# FPGA.net
KiCad netlist of a schematic drawn in Altium Designer
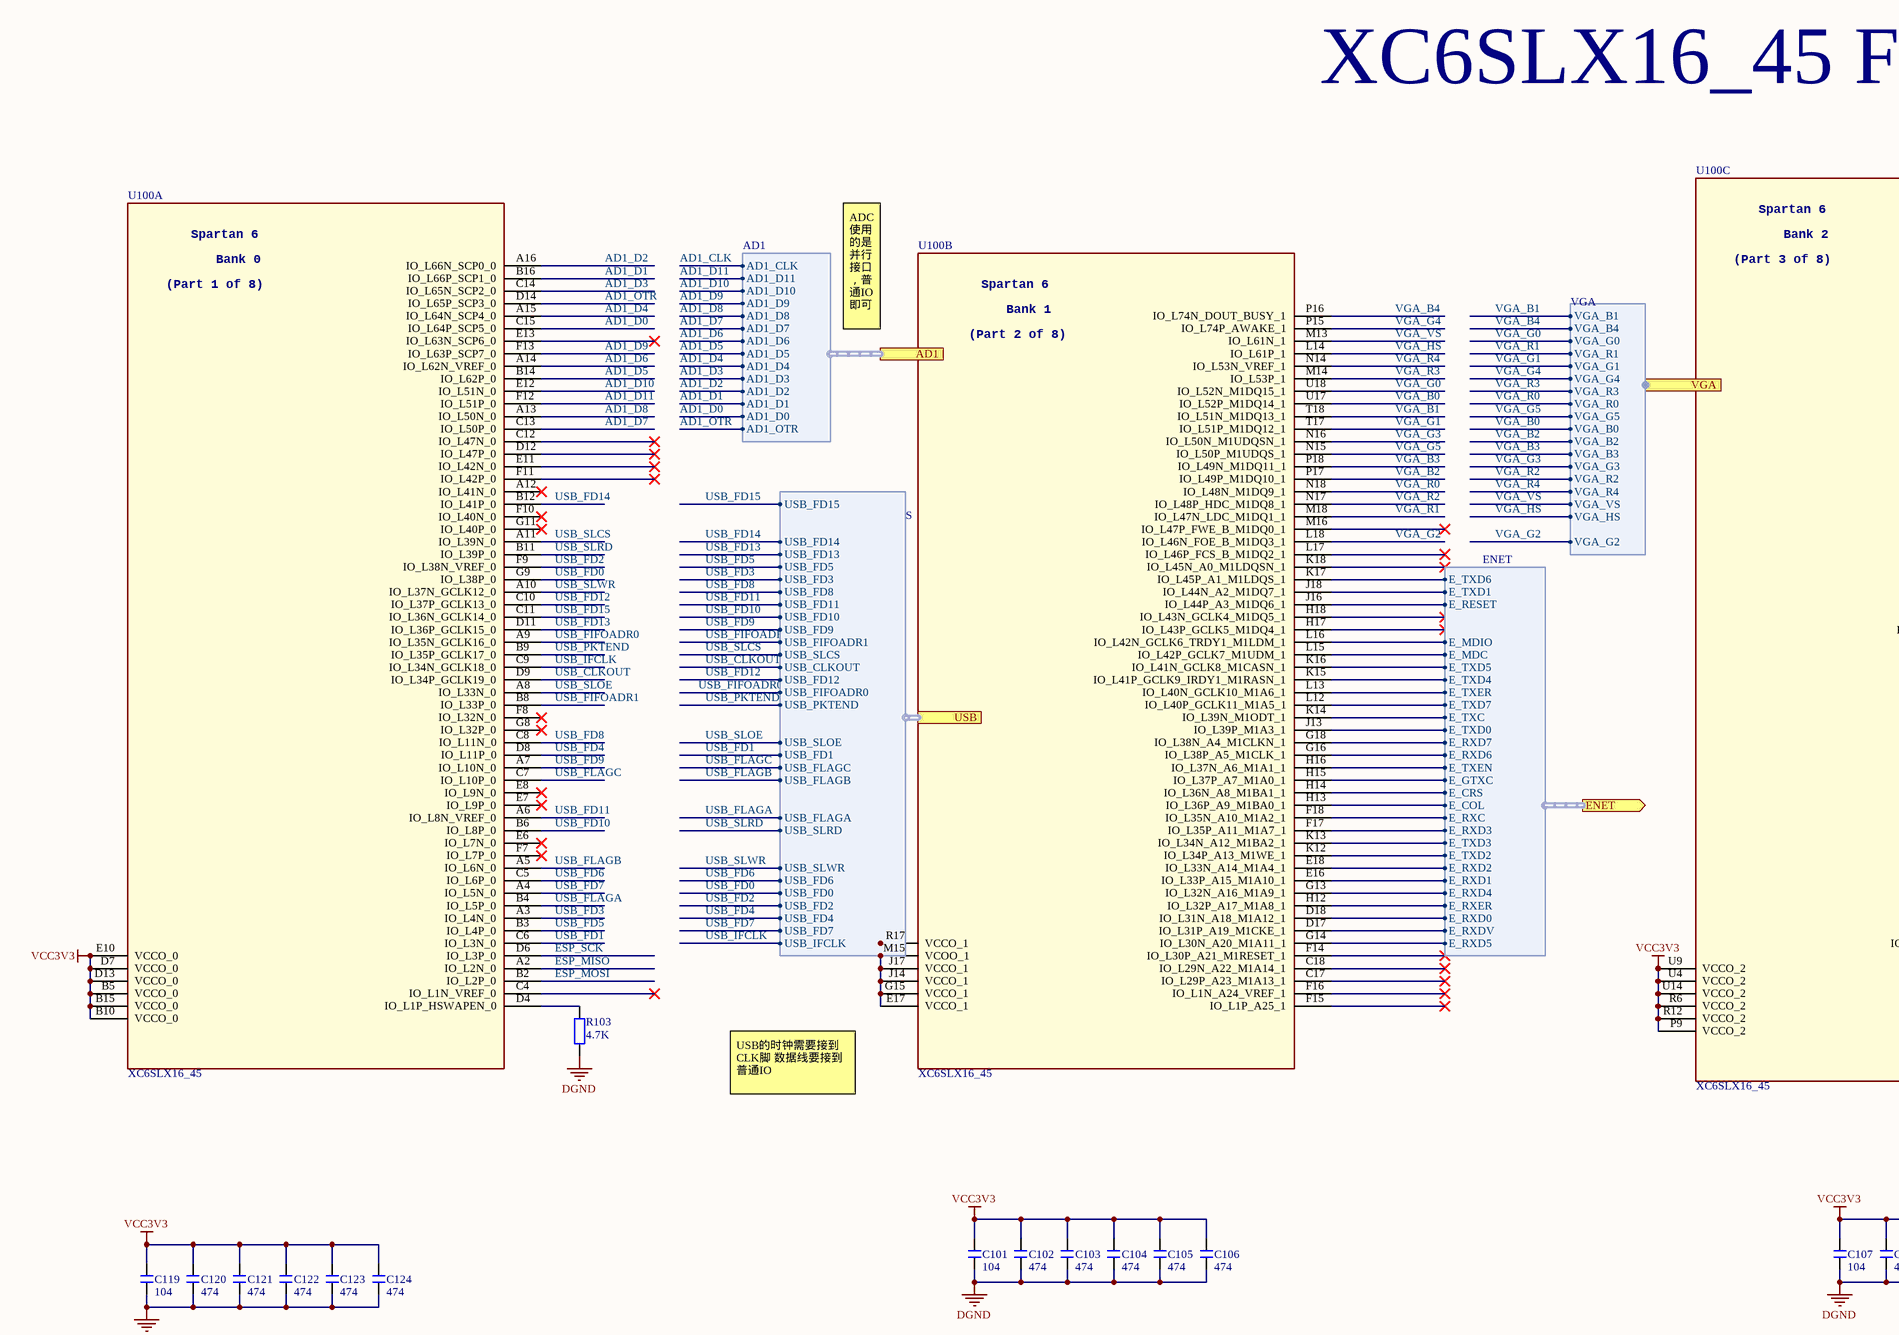
[diagram p0: FPGA.SchDoc, top left]
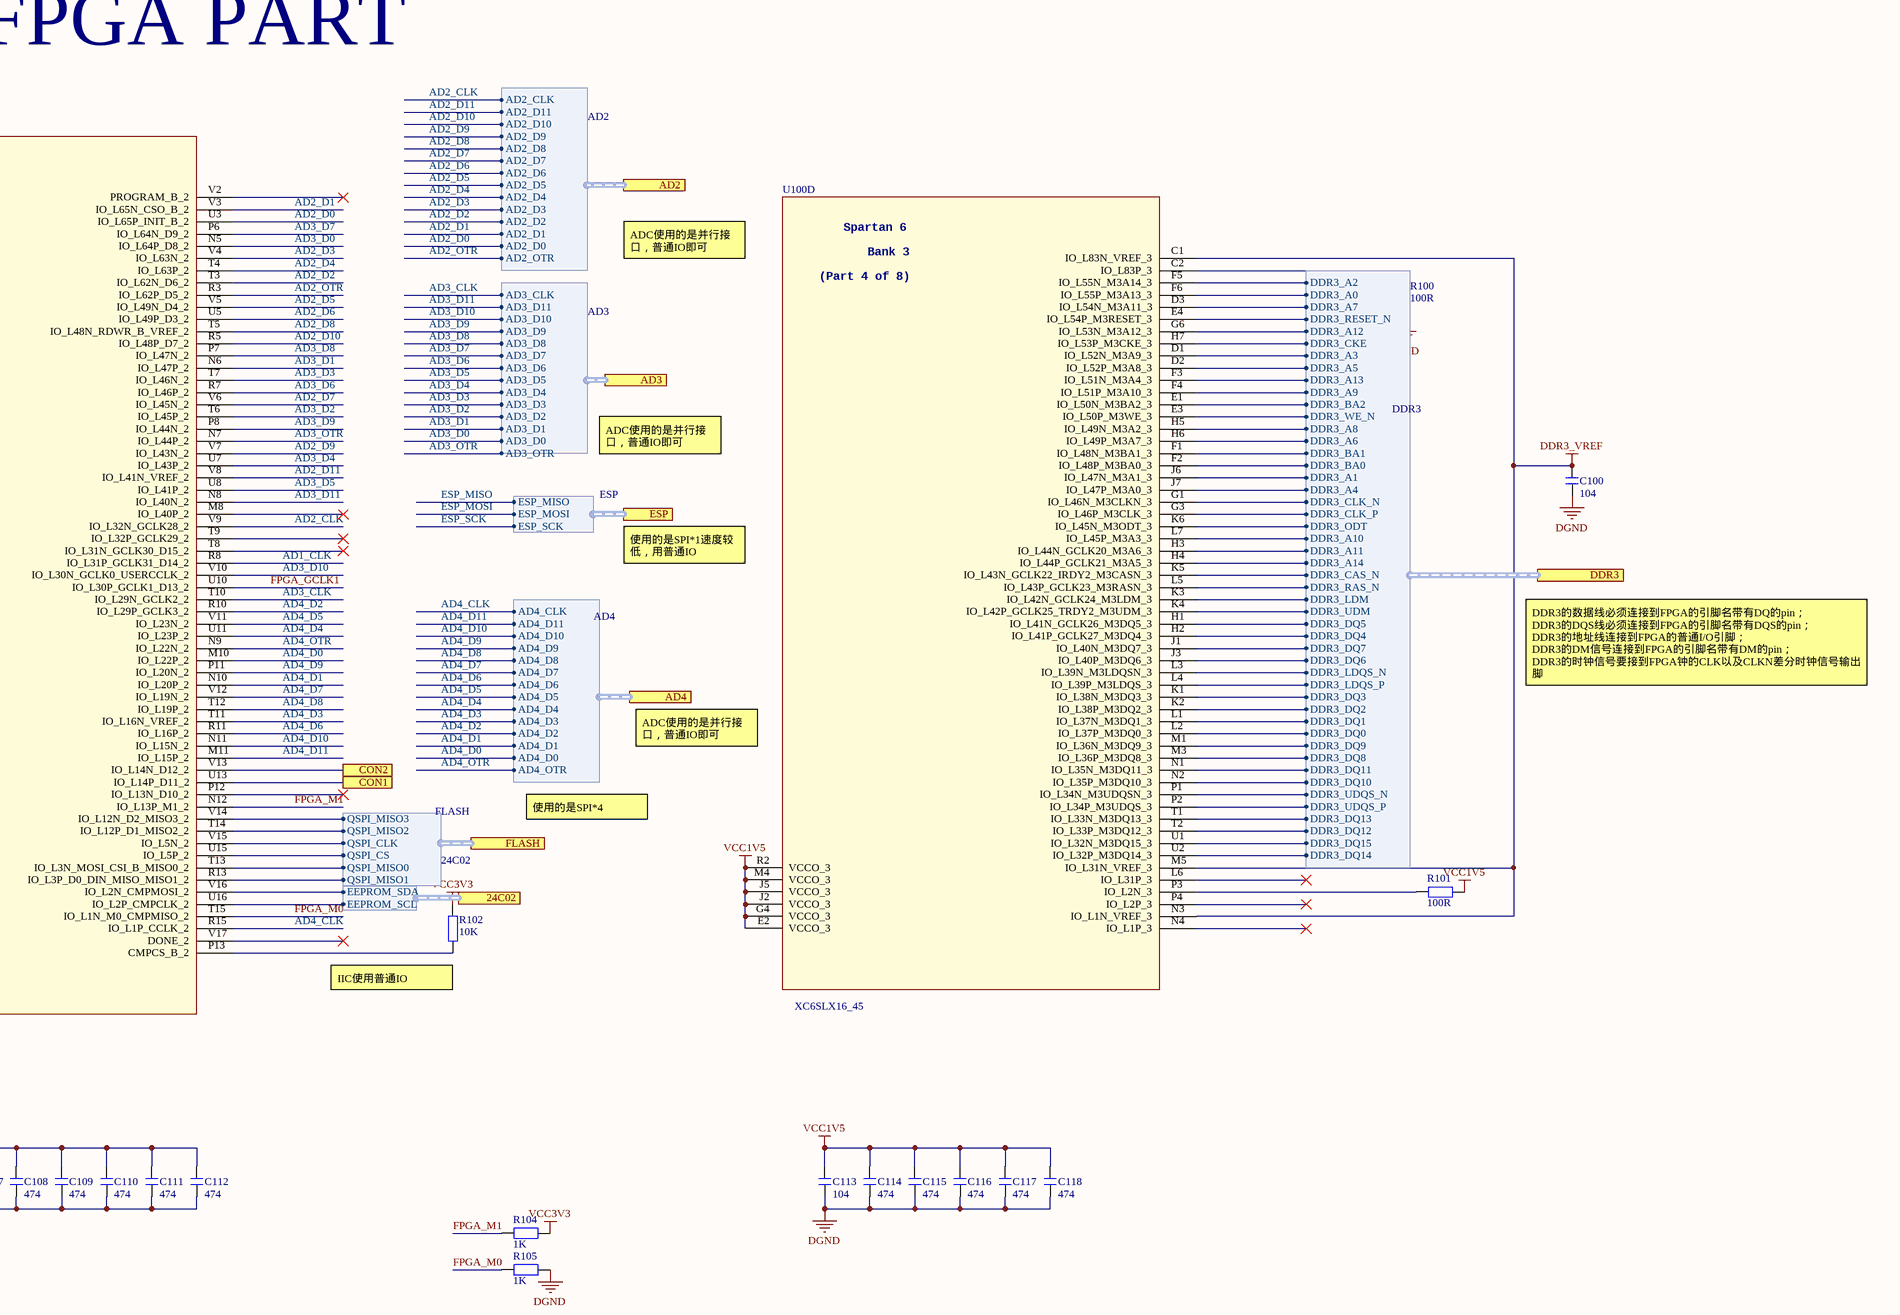
[diagram p1: FPGA.SchDoc, top right]
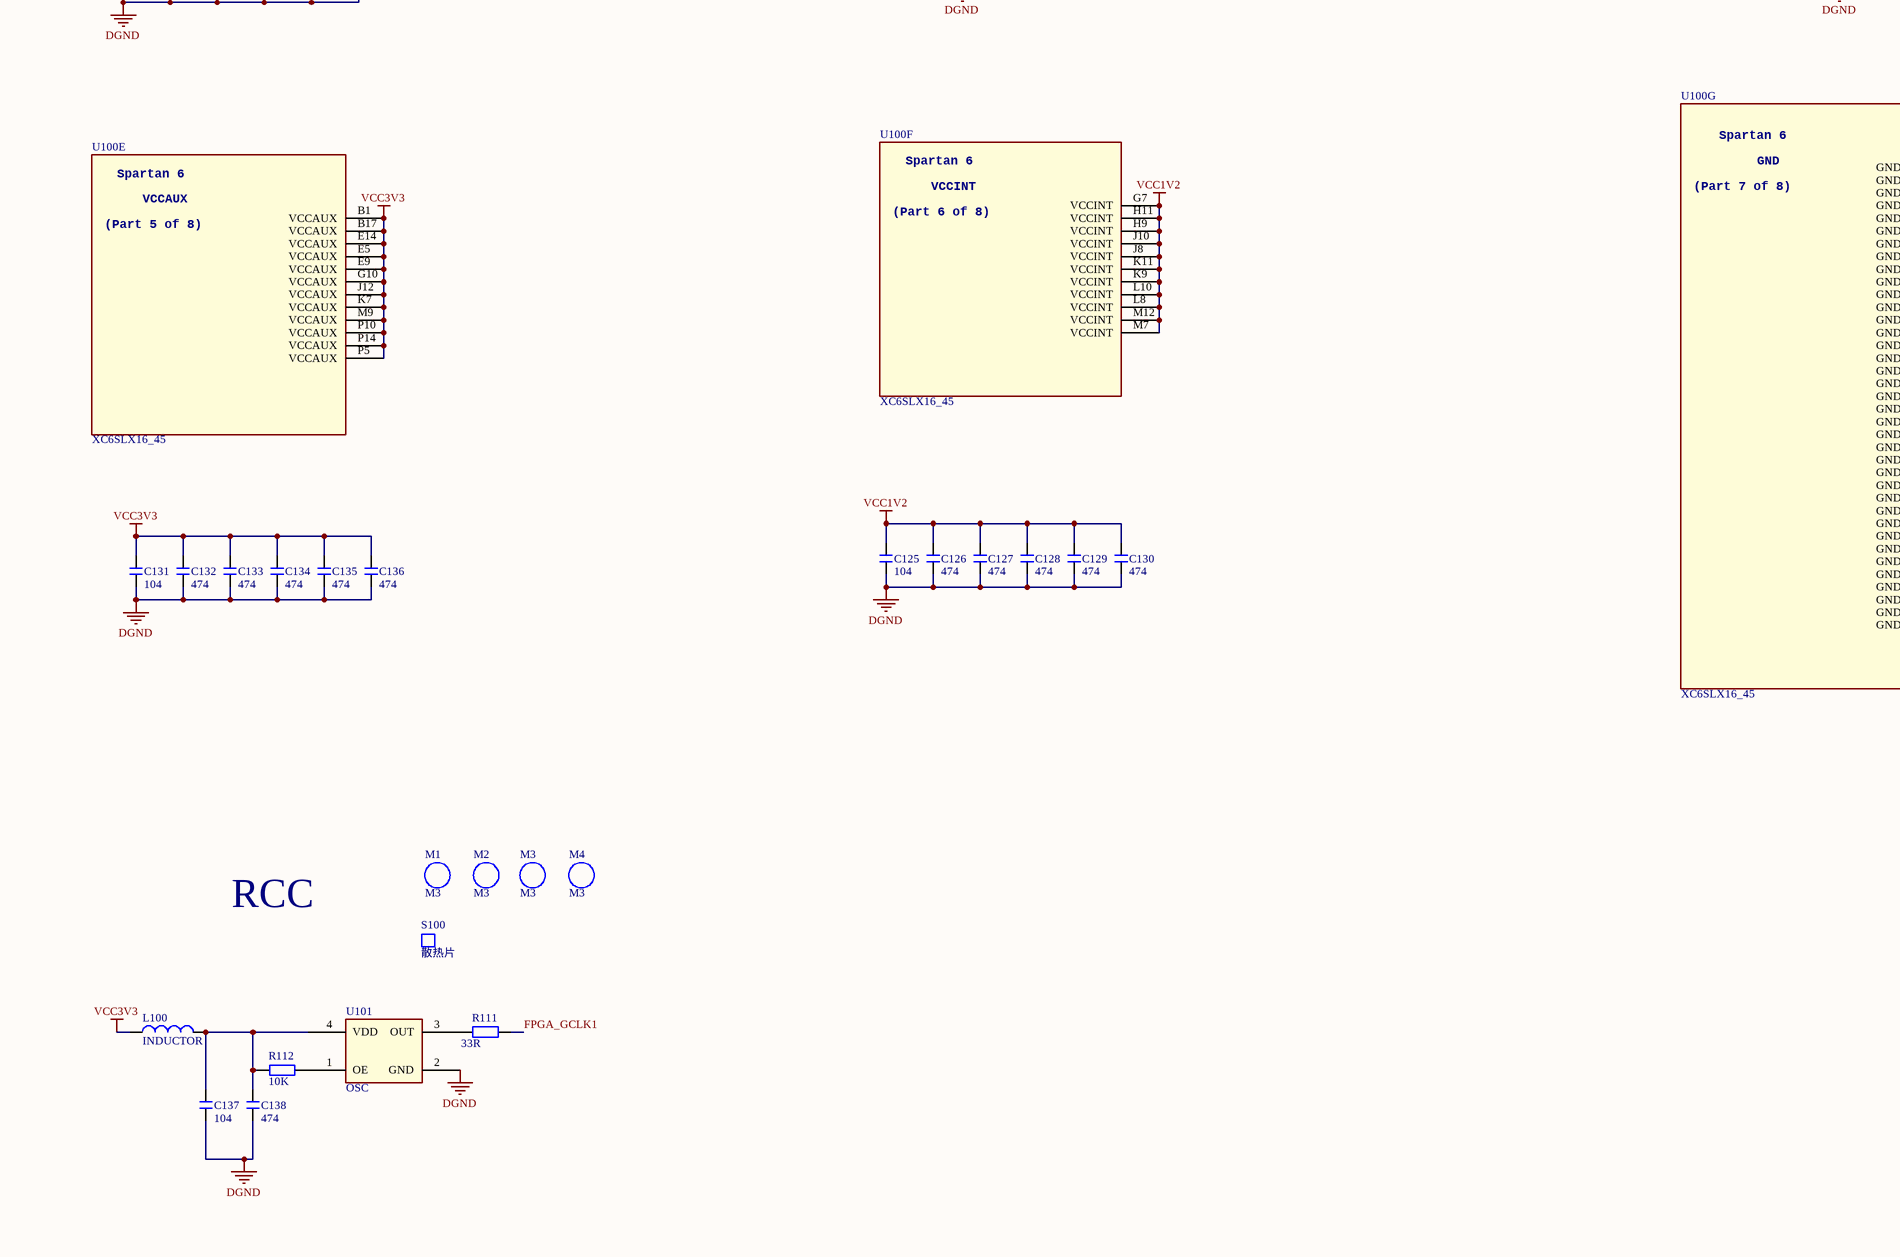
[diagram p2: FPGA.SchDoc, bottom left]
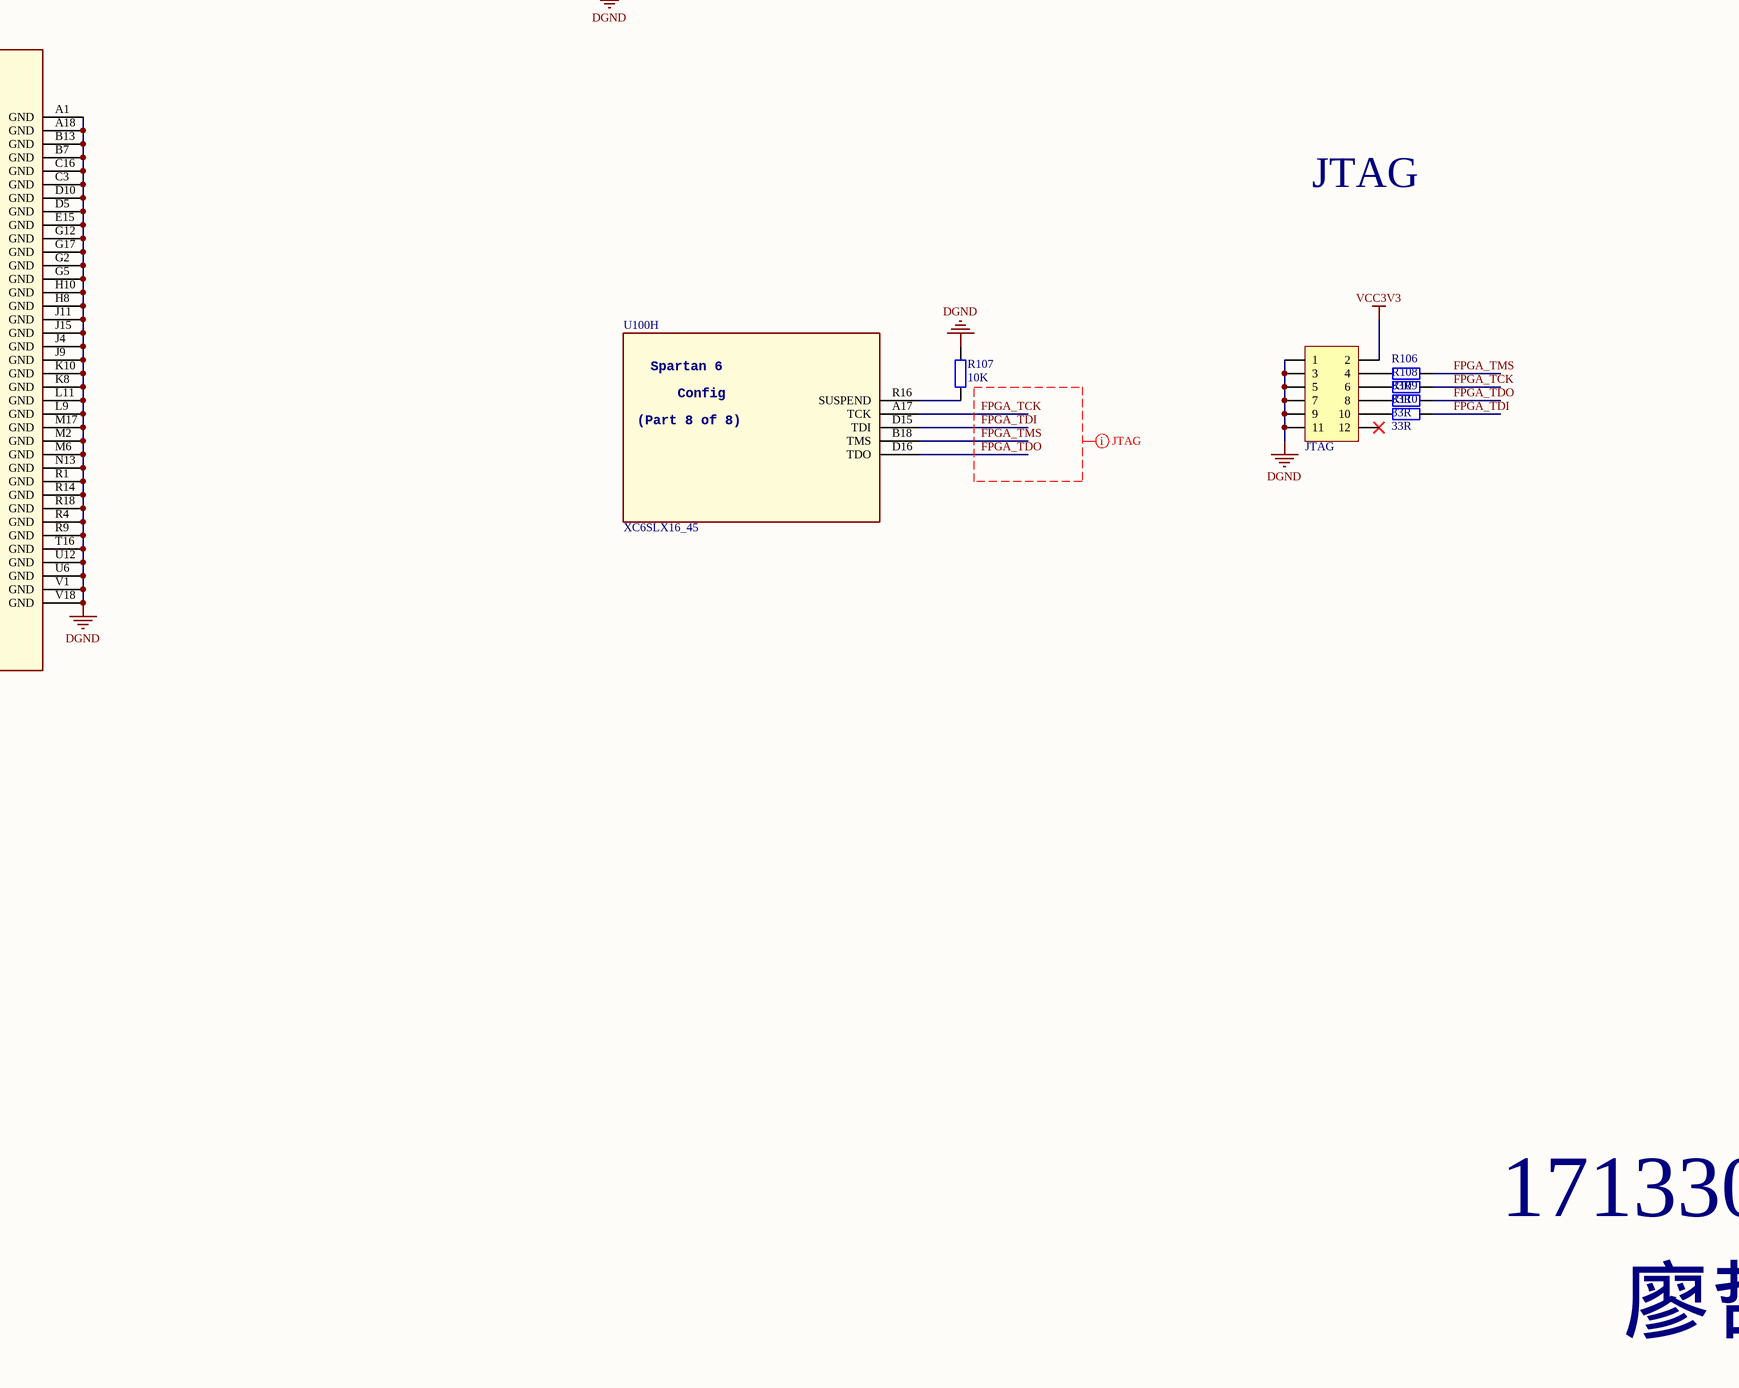
[diagram p3: FPGA.SchDoc, bottom right]

(export (version "E")
  (design (tool "Eeschema 10.0.6"))
  (components
    (comp (ref "C100")
      (value "104")
      (footprint "C 0402_M")
      (description "无极性贴片电容")
      (fields (field (name "版权归属") "源创客"))
      (libsource (lib "3.1   - 电阻-电容-电感") (part "C"))
    )
    (comp (ref "C101")
      (value "104")
      (footprint "C 0402_M")
      (description "无极性贴片电容")
      (fields (field (name "版权归属") "源创客"))
      (libsource (lib "3.1   - 电阻-电容-电感") (part "C"))
    )
    (comp (ref "C102")
      (value "474")
      (footprint "C 0402_M")
      (description "无极性贴片电容")
      (fields (field (name "版权归属") "源创客"))
      (libsource (lib "3.1   - 电阻-电容-电感") (part "C"))
    )
    (comp (ref "C103")
      (value "474")
      (footprint "C 0402_M")
      (description "无极性贴片电容")
      (fields (field (name "版权归属") "源创客"))
      (libsource (lib "3.1   - 电阻-电容-电感") (part "C"))
    )
    (comp (ref "C104")
      (value "474")
      (footprint "C 0402_M")
      (description "无极性贴片电容")
      (fields (field (name "版权归属") "源创客"))
      (libsource (lib "3.1   - 电阻-电容-电感") (part "C"))
    )
    (comp (ref "C105")
      (value "474")
      (footprint "C 0402_M")
      (description "无极性贴片电容")
      (fields (field (name "版权归属") "源创客"))
      (libsource (lib "3.1   - 电阻-电容-电感") (part "C"))
    )
    (comp (ref "C106")
      (value "474")
      (footprint "C 0402_M")
      (description "无极性贴片电容")
      (fields (field (name "版权归属") "源创客"))
      (libsource (lib "3.1   - 电阻-电容-电感") (part "C"))
    )
    (comp (ref "C107")
      (value "104")
      (footprint "C 0402_M")
      (description "无极性贴片电容")
      (fields (field (name "版权归属") "源创客"))
      (libsource (lib "3.1   - 电阻-电容-电感") (part "C"))
    )
    (comp (ref "C108")
      (value "474")
      (footprint "C 0402_M")
      (description "无极性贴片电容")
      (fields (field (name "版权归属") "源创客"))
      (libsource (lib "3.1   - 电阻-电容-电感") (part "C"))
    )
    (comp (ref "C109")
      (value "474")
      (footprint "C 0402_M")
      (description "无极性贴片电容")
      (fields (field (name "版权归属") "源创客"))
      (libsource (lib "3.1   - 电阻-电容-电感") (part "C"))
    )
    (comp (ref "C110")
      (value "474")
      (footprint "C 0402_M")
      (description "无极性贴片电容")
      (fields (field (name "版权归属") "源创客"))
      (libsource (lib "3.1   - 电阻-电容-电感") (part "C"))
    )
    (comp (ref "C111")
      (value "474")
      (footprint "C 0402_M")
      (description "无极性贴片电容")
      (fields (field (name "版权归属") "源创客"))
      (libsource (lib "3.1   - 电阻-电容-电感") (part "C"))
    )
    (comp (ref "C112")
      (value "474")
      (footprint "C 0402_M")
      (description "无极性贴片电容")
      (fields (field (name "版权归属") "源创客"))
      (libsource (lib "3.1   - 电阻-电容-电感") (part "C"))
    )
    (comp (ref "C113")
      (value "104")
      (footprint "C 0402_M")
      (description "无极性贴片电容")
      (fields (field (name "版权归属") "源创客"))
      (libsource (lib "3.1   - 电阻-电容-电感") (part "C"))
    )
    (comp (ref "C114")
      (value "474")
      (footprint "C 0402_M")
      (description "无极性贴片电容")
      (fields (field (name "版权归属") "源创客"))
      (libsource (lib "3.1   - 电阻-电容-电感") (part "C"))
    )
    (comp (ref "C115")
      (value "474")
      (footprint "C 0402_M")
      (description "无极性贴片电容")
      (fields (field (name "版权归属") "源创客"))
      (libsource (lib "3.1   - 电阻-电容-电感") (part "C"))
    )
    (comp (ref "C116")
      (value "474")
      (footprint "C 0402_M")
      (description "无极性贴片电容")
      (fields (field (name "版权归属") "源创客"))
      (libsource (lib "3.1   - 电阻-电容-电感") (part "C"))
    )
    (comp (ref "C117")
      (value "474")
      (footprint "C 0402_M")
      (description "无极性贴片电容")
      (fields (field (name "版权归属") "源创客"))
      (libsource (lib "3.1   - 电阻-电容-电感") (part "C"))
    )
    (comp (ref "C118")
      (value "474")
      (footprint "C 0402_M")
      (description "无极性贴片电容")
      (fields (field (name "版权归属") "源创客"))
      (libsource (lib "3.1   - 电阻-电容-电感") (part "C"))
    )
    (comp (ref "C119")
      (value "104")
      (footprint "C 0402_M")
      (description "无极性贴片电容")
      (fields (field (name "版权归属") "源创客"))
      (libsource (lib "3.1   - 电阻-电容-电感") (part "C"))
    )
    (comp (ref "C120")
      (value "474")
      (footprint "C 0402_M")
      (description "无极性贴片电容")
      (fields (field (name "版权归属") "源创客"))
      (libsource (lib "3.1   - 电阻-电容-电感") (part "C"))
    )
    (comp (ref "C121")
      (value "474")
      (footprint "C 0402_M")
      (description "无极性贴片电容")
      (fields (field (name "版权归属") "源创客"))
      (libsource (lib "3.1   - 电阻-电容-电感") (part "C"))
    )
    (comp (ref "C122")
      (value "474")
      (footprint "C 0402_M")
      (description "无极性贴片电容")
      (fields (field (name "版权归属") "源创客"))
      (libsource (lib "3.1   - 电阻-电容-电感") (part "C"))
    )
    (comp (ref "C123")
      (value "474")
      (footprint "C 0402_M")
      (description "无极性贴片电容")
      (fields (field (name "版权归属") "源创客"))
      (libsource (lib "3.1   - 电阻-电容-电感") (part "C"))
    )
    (comp (ref "C124")
      (value "474")
      (footprint "C 0402_M")
      (description "无极性贴片电容")
      (fields (field (name "版权归属") "源创客"))
      (libsource (lib "3.1   - 电阻-电容-电感") (part "C"))
    )
    (comp (ref "C125")
      (value "104")
      (footprint "C 0402_M")
      (description "无极性贴片电容")
      (fields (field (name "版权归属") "源创客"))
      (libsource (lib "3.1   - 电阻-电容-电感") (part "C"))
    )
    (comp (ref "C126")
      (value "474")
      (footprint "C 0402_M")
      (description "无极性贴片电容")
      (fields (field (name "版权归属") "源创客"))
      (libsource (lib "3.1   - 电阻-电容-电感") (part "C"))
    )
    (comp (ref "C127")
      (value "474")
      (footprint "C 0402_M")
      (description "无极性贴片电容")
      (fields (field (name "版权归属") "源创客"))
      (libsource (lib "3.1   - 电阻-电容-电感") (part "C"))
    )
    (comp (ref "C128")
      (value "474")
      (footprint "C 0402_M")
      (description "无极性贴片电容")
      (fields (field (name "版权归属") "源创客"))
      (libsource (lib "3.1   - 电阻-电容-电感") (part "C"))
    )
    (comp (ref "C129")
      (value "474")
      (footprint "C 0402_M")
      (description "无极性贴片电容")
      (fields (field (name "版权归属") "源创客"))
      (libsource (lib "3.1   - 电阻-电容-电感") (part "C"))
    )
    (comp (ref "C130")
      (value "474")
      (footprint "C 0402_M")
      (description "无极性贴片电容")
      (fields (field (name "版权归属") "源创客"))
      (libsource (lib "3.1   - 电阻-电容-电感") (part "C"))
    )
    (comp (ref "C131")
      (value "104")
      (footprint "C 0402_M")
      (description "无极性贴片电容")
      (fields (field (name "版权归属") "源创客"))
      (libsource (lib "3.1   - 电阻-电容-电感") (part "C"))
    )
    (comp (ref "C132")
      (value "474")
      (footprint "C 0402_M")
      (description "无极性贴片电容")
      (fields (field (name "版权归属") "源创客"))
      (libsource (lib "3.1   - 电阻-电容-电感") (part "C"))
    )
    (comp (ref "C133")
      (value "474")
      (footprint "C 0402_M")
      (description "无极性贴片电容")
      (fields (field (name "版权归属") "源创客"))
      (libsource (lib "3.1   - 电阻-电容-电感") (part "C"))
    )
    (comp (ref "C134")
      (value "474")
      (footprint "C 0402_M")
      (description "无极性贴片电容")
      (fields (field (name "版权归属") "源创客"))
      (libsource (lib "3.1   - 电阻-电容-电感") (part "C"))
    )
    (comp (ref "C135")
      (value "474")
      (footprint "C 0402_M")
      (description "无极性贴片电容")
      (fields (field (name "版权归属") "源创客"))
      (libsource (lib "3.1   - 电阻-电容-电感") (part "C"))
    )
    (comp (ref "C136")
      (value "474")
      (footprint "C 0402_M")
      (description "无极性贴片电容")
      (fields (field (name "版权归属") "源创客"))
      (libsource (lib "3.1   - 电阻-电容-电感") (part "C"))
    )
    (comp (ref "C137")
      (value "104")
      (footprint "C 0402_M")
      (description "无极性贴片电容")
      (fields (field (name "版权归属") "源创客"))
      (libsource (lib "3.1   - 电阻-电容-电感") (part "C"))
    )
    (comp (ref "C138")
      (value "474")
      (footprint "C 0402_M")
      (description "无极性贴片电容")
      (fields (field (name "版权归属") "源创客"))
      (libsource (lib "3.1   - 电阻-电容-电感") (part "C"))
    )
    (comp (ref "JTAG")
      (value "Header 6X2")
      (footprint "IDC2.54-LI-2x6P")
      (description "6*2P接插件")
      (fields (field (name "版权归属") "源创客"))
      (libsource (lib "4.5   - 接插件-脚距2.54") (part "Header  6X2"))
    )
    (comp (ref "L100")
      (value "INDUCTOR")
      (footprint "L 0805")
      (libsource (lib "altium-import") (part "root_1_INDUCTOR_"))
    )
    (comp (ref "M1")
      (value "M3")
      (footprint "M3 140X350")
      (description "铜柱孔")
      (fields (field (name "版权归属") "源创客"))
      (libsource (lib "15.1 - 未分类器件") (part "M3"))
    )
    (comp (ref "M2")
      (value "M3")
      (footprint "M3 140X350")
      (description "铜柱孔")
      (fields (field (name "版权归属") "源创客"))
      (libsource (lib "15.1 - 未分类器件") (part "M3"))
    )
    (comp (ref "M3")
      (value "M3")
      (footprint "M3 140X350")
      (description "铜柱孔")
      (fields (field (name "版权归属") "源创客"))
      (libsource (lib "15.1 - 未分类器件") (part "M3"))
    )
    (comp (ref "M4")
      (value "M3")
      (footprint "M3 140X350")
      (description "铜柱孔")
      (fields (field (name "版权归属") "源创客"))
      (libsource (lib "15.1 - 未分类器件") (part "M3"))
    )
    (comp (ref "R100")
      (value "100R")
      (footprint "R 0402_M")
      (description "贴片电阻")
      (fields (field (name "版权归属") "源创客"))
      (libsource (lib "3.1   - 电阻-电容-电感") (part "R"))
    )
    (comp (ref "R101")
      (value "100R")
      (footprint "R 0402_M")
      (description "贴片电阻")
      (fields (field (name "版权归属") "源创客"))
      (libsource (lib "3.1   - 电阻-电容-电感") (part "R"))
    )
    (comp (ref "R102")
      (value "10K")
      (footprint "R 0402_M")
      (description "贴片电阻")
      (fields (field (name "版权归属") "源创客"))
      (libsource (lib "3.1   - 电阻-电容-电感") (part "R"))
    )
    (comp (ref "R103")
      (value "4.7K")
      (footprint "R 0402_M")
      (description "贴片电阻")
      (fields (field (name "版权归属") "源创客"))
      (libsource (lib "3.1   - 电阻-电容-电感") (part "R"))
    )
    (comp (ref "R104")
      (value "1K")
      (footprint "R 0402_M")
      (description "贴片电阻")
      (fields (field (name "版权归属") "源创客"))
      (libsource (lib "3.1   - 电阻-电容-电感") (part "R"))
    )
    (comp (ref "R105")
      (value "1K")
      (footprint "R 0402_M")
      (description "贴片电阻")
      (fields (field (name "版权归属") "源创客"))
      (libsource (lib "3.1   - 电阻-电容-电感") (part "R"))
    )
    (comp (ref "R106")
      (value "33R")
      (footprint "R 0402_M")
      (description "贴片电阻")
      (fields (field (name "版权归属") "源创客"))
      (libsource (lib "3.1   - 电阻-电容-电感") (part "R"))
    )
    (comp (ref "R107")
      (value "10K")
      (footprint "R 0402_M")
      (description "贴片电阻")
      (fields (field (name "版权归属") "源创客"))
      (libsource (lib "3.1   - 电阻-电容-电感") (part "R"))
    )
    (comp (ref "R108")
      (value "33R")
      (footprint "R 0402_M")
      (description "贴片电阻")
      (fields (field (name "版权归属") "源创客"))
      (libsource (lib "3.1   - 电阻-电容-电感") (part "R"))
    )
    (comp (ref "R109")
      (value "33R")
      (footprint "R 0402_M")
      (description "贴片电阻")
      (fields (field (name "版权归属") "源创客"))
      (libsource (lib "3.1   - 电阻-电容-电感") (part "R"))
    )
    (comp (ref "R110")
      (value "33R")
      (footprint "R 0402_M")
      (description "贴片电阻")
      (fields (field (name "版权归属") "源创客"))
      (libsource (lib "3.1   - 电阻-电容-电感") (part "R"))
    )
    (comp (ref "R111")
      (value "33R")
      (footprint "R 0402_M")
      (description "贴片电阻")
      (fields (field (name "版权归属") "源创客"))
      (libsource (lib "3.1   - 电阻-电容-电感") (part "R"))
    )
    (comp (ref "R112")
      (value "10K")
      (footprint "R 0402_M")
      (description "贴片电阻")
      (fields (field (name "版权归属") "源创客"))
      (libsource (lib "3.1   - 电阻-电容-电感") (part "R"))
    )
    (comp (ref "S100")
      (value "散热片")
      (footprint "SRP10-15-21")
      (fields (field (name "版权归属") "源创客"))
      (libsource (lib "15.1 - 未分类器件") (part "S1"))
    )
    (comp (ref "U100")
      (value "XC6SLX16_45")
      (footprint "BGA324C80P18X18_1500X1500X150")
      (libsource (lib "altium-import") (part "root_0_XC6SLX16_45_"))
    )
    (comp (ref "U101")
      (value "OSC")
      (footprint "OSC 8045-4P")
      (libsource (lib "altium-import") (part "root_0_OSC_"))
    )
  )
  (nets
    (net (code "12") (name "/AD1_CLK") (class "Default")
      (node (ref "U100") (pin "R8") (pinfunction "IO_L31P_GCLK31_D14_2_R8") (pintype "passive"))
    )
    (net (code "13") (name "/AD1_D0") (class "Default")
      (node (ref "U100") (pin "C15") (pinfunction "IO_L64P_SCP5_0_C15") (pintype "passive"))
    )
    (net (code "14") (name "/AD1_D1") (class "Default")
      (node (ref "U100") (pin "B16") (pinfunction "IO_L66P_SCP1_0_B16") (pintype "passive"))
    )
    (net (code "15") (name "/AD1_D2") (class "Default")
      (node (ref "U100") (pin "A16") (pinfunction "IO_L66N_SCP0_0_A16") (pintype "passive"))
    )
    (net (code "16") (name "/AD1_D3") (class "Default")
      (node (ref "U100") (pin "C14") (pinfunction "IO_L65N_SCP2_0_C14") (pintype "passive"))
    )
    (net (code "17") (name "/AD1_D4") (class "Default")
      (node (ref "U100") (pin "A15") (pinfunction "IO_L64N_SCP4_0_A15") (pintype "passive"))
    )
    (net (code "18") (name "/AD1_D5") (class "Default")
      (node (ref "U100") (pin "B14") (pinfunction "IO_L62P_0_B14") (pintype "passive"))
    )
    (net (code "19") (name "/AD1_D6") (class "Default")
      (node (ref "U100") (pin "A14") (pinfunction "IO_L62N_VREF_0_A14") (pintype "passive"))
    )
    (net (code "20") (name "/AD1_D7") (class "Default")
      (node (ref "U100") (pin "C13") (pinfunction "IO_L50P_0_C13") (pintype "passive"))
    )
    (net (code "21") (name "/AD1_D8") (class "Default")
      (node (ref "U100") (pin "A13") (pinfunction "IO_L50N_0_A13") (pintype "passive"))
    )
    (net (code "22") (name "/AD1_D9") (class "Default")
      (node (ref "U100") (pin "F13") (pinfunction "IO_L63P_SCP7_0_F13") (pintype "passive"))
    )
    (net (code "23") (name "/AD1_D10") (class "Default")
      (node (ref "U100") (pin "E12") (pinfunction "IO_L51N_0_E12") (pintype "passive"))
    )
    (net (code "24") (name "/AD1_D11") (class "Default")
      (node (ref "U100") (pin "F12") (pinfunction "IO_L51P_0_F12") (pintype "passive"))
    )
    (net (code "25") (name "/AD1_OTR") (class "Default")
      (node (ref "U100") (pin "D14") (pinfunction "IO_L65P_SCP3_0_D14") (pintype "passive"))
    )
    (net (code "26") (name "/AD2_CLK") (class "Default")
      (node (ref "U100") (pin "V9") (pinfunction "IO_L32N_GCLK28_2_V9") (pintype "passive"))
    )
    (net (code "27") (name "/AD2_D0") (class "Default")
      (node (ref "U100") (pin "U3") (pinfunction "IO_L65P_INIT_B_2_U3") (pintype "passive"))
    )
    (net (code "28") (name "/AD2_D1") (class "Default")
      (node (ref "U100") (pin "V3") (pinfunction "IO_L65N_CSO_B_2_V3") (pintype "passive"))
    )
    (net (code "29") (name "/AD2_D2") (class "Default")
      (node (ref "U100") (pin "T3") (pinfunction "IO_L62N_D6_2_T3") (pintype "passive"))
    )
    (net (code "30") (name "/AD2_D3") (class "Default")
      (node (ref "U100") (pin "V4") (pinfunction "IO_L63N_2_V4") (pintype "passive"))
    )
    (net (code "31") (name "/AD2_D4") (class "Default")
      (node (ref "U100") (pin "T4") (pinfunction "IO_L63P_2_T4") (pintype "passive"))
    )
    (net (code "32") (name "/AD2_D5") (class "Default")
      (node (ref "U100") (pin "V5") (pinfunction "IO_L49N_D4_2_V5") (pintype "passive"))
    )
    (net (code "33") (name "/AD2_D6") (class "Default")
      (node (ref "U100") (pin "U5") (pinfunction "IO_L49P_D3_2_U5") (pintype "passive"))
    )
    (net (code "34") (name "/AD2_D7") (class "Default")
      (node (ref "U100") (pin "V6") (pinfunction "IO_L45N_2_V6") (pintype "passive"))
    )
    (net (code "35") (name "/AD2_D8") (class "Default")
      (node (ref "U100") (pin "T5") (pinfunction "IO_L48N_RDWR_B_VREF_2_T5") (pintype "passive"))
    )
    (net (code "36") (name "/AD2_D9") (class "Default")
      (node (ref "U100") (pin "V7") (pinfunction "IO_L43N_2_V7") (pintype "passive"))
    )
    (net (code "37") (name "/AD2_D10") (class "Default")
      (node (ref "U100") (pin "R5") (pinfunction "IO_L48P_D7_2_R5") (pintype "passive"))
    )
    (net (code "38") (name "/AD2_D11") (class "Default")
      (node (ref "U100") (pin "V8") (pinfunction "IO_L41N_VREF_2_V8") (pintype "passive"))
    )
    (net (code "39") (name "/AD2_OTR") (class "Default")
      (node (ref "U100") (pin "R3") (pinfunction "IO_L62P_D5_2_R3") (pintype "passive"))
    )
    (net (code "40") (name "/AD3_CLK") (class "Default")
      (node (ref "U100") (pin "T10") (pinfunction "IO_L29N_GCLK2_2_T10") (pintype "passive"))
    )
    (net (code "41") (name "/AD3_D0") (class "Default")
      (node (ref "U100") (pin "N5") (pinfunction "IO_L64P_D8_2_N5") (pintype "passive"))
    )
    (net (code "42") (name "/AD3_D1") (class "Default")
      (node (ref "U100") (pin "N6") (pinfunction "IO_L47P_2_N6") (pintype "passive"))
    )
    (net (code "43") (name "/AD3_D2") (class "Default")
      (node (ref "U100") (pin "T6") (pinfunction "IO_L45P_2_T6") (pintype "passive"))
    )
    (net (code "44") (name "/AD3_D3") (class "Default")
      (node (ref "U100") (pin "T7") (pinfunction "IO_L46N_2_T7") (pintype "passive"))
    )
    (net (code "45") (name "/AD3_D4") (class "Default")
      (node (ref "U100") (pin "U7") (pinfunction "IO_L43P_2_U7") (pintype "passive"))
    )
    (net (code "46") (name "/AD3_D5") (class "Default")
      (node (ref "U100") (pin "U8") (pinfunction "IO_L41P_2_U8") (pintype "passive"))
    )
    (net (code "47") (name "/AD3_D6") (class "Default")
      (node (ref "U100") (pin "R7") (pinfunction "IO_L46P_2_R7") (pintype "passive"))
    )
    (net (code "48") (name "/AD3_D7") (class "Default")
      (node (ref "U100") (pin "P6") (pinfunction "IO_L64N_D9_2_P6") (pintype "passive"))
    )
    (net (code "49") (name "/AD3_D8") (class "Default")
      (node (ref "U100") (pin "P7") (pinfunction "IO_L47N_2_P7") (pintype "passive"))
    )
    (net (code "50") (name "/AD3_D9") (class "Default")
      (node (ref "U100") (pin "P8") (pinfunction "IO_L44N_2_P8") (pintype "passive"))
    )
    (net (code "51") (name "/AD3_D10") (class "Default")
      (node (ref "U100") (pin "V10") (pinfunction "IO_L30N_GCLK0_USERCCLK_2_V10") (pintype "passive"))
    )
    (net (code "52") (name "/AD3_D11") (class "Default")
      (node (ref "U100") (pin "N8") (pinfunction "IO_L40N_2_N8") (pintype "passive"))
    )
    (net (code "53") (name "/AD3_OTR") (class "Default")
      (node (ref "U100") (pin "N7") (pinfunction "IO_L44P_2_N7") (pintype "passive"))
    )
    (net (code "54") (name "/AD4_CLK") (class "Default")
      (node (ref "U100") (pin "R15") (pinfunction "IO_L1P_CCLK_2_R15") (pintype "passive"))
    )
    (net (code "55") (name "/AD4_D0") (class "Default")
      (node (ref "U100") (pin "M10") (pinfunction "IO_L22P_2_M10") (pintype "passive"))
    )
    (net (code "56") (name "/AD4_D1") (class "Default")
      (node (ref "U100") (pin "N10") (pinfunction "IO_L20P_2_N10") (pintype "passive"))
    )
    (net (code "57") (name "/AD4_D2") (class "Default")
      (node (ref "U100") (pin "R10") (pinfunction "IO_L29P_GCLK3_2_R10") (pintype "passive"))
    )
    (net (code "58") (name "/AD4_D3") (class "Default")
      (node (ref "U100") (pin "T11") (pinfunction "IO_L16N_VREF_2_T11") (pintype "passive"))
    )
    (net (code "59") (name "/AD4_D4") (class "Default")
      (node (ref "U100") (pin "U11") (pinfunction "IO_L23P_2_U11") (pintype "passive"))
    )
    (net (code "60") (name "/AD4_D5") (class "Default")
      (node (ref "U100") (pin "V11") (pinfunction "IO_L23N_2_V11") (pintype "passive"))
    )
    (net (code "61") (name "/AD4_D6") (class "Default")
      (node (ref "U100") (pin "R11") (pinfunction "IO_L16P_2_R11") (pintype "passive"))
    )
    (net (code "62") (name "/AD4_D7") (class "Default")
      (node (ref "U100") (pin "V12") (pinfunction "IO_L19N_2_V12") (pintype "passive"))
    )
    (net (code "63") (name "/AD4_D8") (class "Default")
      (node (ref "U100") (pin "T12") (pinfunction "IO_L19P_2_T12") (pintype "passive"))
    )
    (net (code "64") (name "/AD4_D9") (class "Default")
      (node (ref "U100") (pin "P11") (pinfunction "IO_L20N_2_P11") (pintype "passive"))
    )
    (net (code "65") (name "/AD4_D10") (class "Default")
      (node (ref "U100") (pin "N11") (pinfunction "IO_L15N_2_N11") (pintype "passive"))
    )
    (net (code "66") (name "/AD4_D11") (class "Default")
      (node (ref "U100") (pin "M11") (pinfunction "IO_L15P_2_M11") (pintype "passive"))
    )
    (net (code "67") (name "/AD4_OTR") (class "Default")
      (node (ref "U100") (pin "N9") (pinfunction "IO_L22N_2_N9") (pintype "passive"))
    )
    (net (code "68") (name "/CON1") (class "Default")
      (node (ref "U100") (pin "U13") (pinfunction "IO_L14P_D11_2_U13") (pintype "passive"))
    )
    (net (code "69") (name "/CON2") (class "Default")
      (node (ref "U100") (pin "V13") (pinfunction "IO_L14N_D12_2_V13") (pintype "passive"))
    )
    (net (code "70") (name "/DDR3_A0") (class "Default")
      (node (ref "U100") (pin "F6") (pinfunction "IO_L55P_M3A13_3_F6") (pintype "passive"))
    )
    (net (code "71") (name "/DDR3_A1") (class "Default")
      (node (ref "U100") (pin "J6") (pinfunction "IO_L47N_M3A1_3_J6") (pintype "passive"))
    )
    (net (code "72") (name "/DDR3_A2") (class "Default")
      (node (ref "U100") (pin "F5") (pinfunction "IO_L55N_M3A14_3_F5") (pintype "passive"))
    )
    (net (code "73") (name "/DDR3_A3") (class "Default")
      (node (ref "U100") (pin "D1") (pinfunction "IO_L52N_M3A9_3_D1") (pintype "passive"))
    )
    (net (code "74") (name "/DDR3_A4") (class "Default")
      (node (ref "U100") (pin "J7") (pinfunction "IO_L47P_M3A0_3_J7") (pintype "passive"))
    )
    (net (code "75") (name "/DDR3_A5") (class "Default")
      (node (ref "U100") (pin "D2") (pinfunction "IO_L52P_M3A8_3_D2") (pintype "passive"))
    )
    (net (code "76") (name "/DDR3_A6") (class "Default")
      (node (ref "U100") (pin "H6") (pinfunction "IO_L49P_M3A7_3_H6") (pintype "passive"))
    )
    (net (code "77") (name "/DDR3_A7") (class "Default")
      (node (ref "U100") (pin "D3") (pinfunction "IO_L54N_M3A11_3_D3") (pintype "passive"))
    )
    (net (code "78") (name "/DDR3_A8") (class "Default")
      (node (ref "U100") (pin "H5") (pinfunction "IO_L49N_M3A2_3_H5") (pintype "passive"))
    )
    (net (code "79") (name "/DDR3_A9") (class "Default")
      (node (ref "U100") (pin "F4") (pinfunction "IO_L51P_M3A10_3_F4") (pintype "passive"))
    )
    (net (code "80") (name "/DDR3_A10") (class "Default")
      (node (ref "U100") (pin "L7") (pinfunction "IO_L45P_M3A3_3_L7") (pintype "passive"))
    )
    (net (code "81") (name "/DDR3_A11") (class "Default")
      (node (ref "U100") (pin "H3") (pinfunction "IO_L44N_GCLK20_M3A6_3_H3") (pintype "passive"))
    )
    (net (code "82") (name "/DDR3_A12") (class "Default")
      (node (ref "U100") (pin "G6") (pinfunction "IO_L53N_M3A12_3_G6") (pintype "passive"))
    )
    (net (code "83") (name "/DDR3_A13") (class "Default")
      (node (ref "U100") (pin "F3") (pinfunction "IO_L51N_M3A4_3_F3") (pintype "passive"))
    )
    (net (code "84") (name "/DDR3_A14") (class "Default")
      (node (ref "U100") (pin "H4") (pinfunction "IO_L44P_GCLK21_M3A5_3_H4") (pintype "passive"))
    )
    (net (code "85") (name "/DDR3_BA0") (class "Default")
      (node (ref "U100") (pin "F2") (pinfunction "IO_L48P_M3BA0_3_F2") (pintype "passive"))
    )
    (net (code "86") (name "/DDR3_BA1") (class "Default")
      (node (ref "U100") (pin "F1") (pinfunction "IO_L48N_M3BA1_3_F1") (pintype "passive"))
    )
    (net (code "87") (name "/DDR3_BA2") (class "Default")
      (node (ref "U100") (pin "E1") (pinfunction "IO_L50N_M3BA2_3_E1") (pintype "passive"))
    )
    (net (code "88") (name "/DDR3_CAS_N") (class "Default")
      (node (ref "U100") (pin "K5") (pinfunction "IO_L43N_GCLK22_IRDY2_M3CASN_3_K5") (pintype "passive"))
    )
    (net (code "89") (name "/DDR3_CKE") (class "Default")
      (node (ref "U100") (pin "H7") (pinfunction "IO_L53P_M3CKE_3_H7") (pintype "passive"))
    )
    (net (code "90") (name "/DDR3_CLK_N") (class "Default")
      (node (ref "U100") (pin "G1") (pinfunction "IO_L46N_M3CLKN_3_G1") (pintype "passive"))
    )
    (net (code "91") (name "/DDR3_CLK_P") (class "Default")
      (node (ref "U100") (pin "G3") (pinfunction "IO_L46P_M3CLK_3_G3") (pintype "passive"))
    )
    (net (code "92") (name "/DDR3_DQ0") (class "Default")
      (node (ref "U100") (pin "L2") (pinfunction "IO_L37P_M3DQ0_3_L2") (pintype "passive"))
    )
    (net (code "93") (name "/DDR3_DQ1") (class "Default")
      (node (ref "U100") (pin "L1") (pinfunction "IO_L37N_M3DQ1_3_L1") (pintype "passive"))
    )
    (net (code "94") (name "/DDR3_DQ2") (class "Default")
      (node (ref "U100") (pin "K2") (pinfunction "IO_L38P_M3DQ2_3_K2") (pintype "passive"))
    )
    (net (code "95") (name "/DDR3_DQ3") (class "Default")
      (node (ref "U100") (pin "K1") (pinfunction "IO_L38N_M3DQ3_3_K1") (pintype "passive"))
    )
    (net (code "96") (name "/DDR3_DQ4") (class "Default")
      (node (ref "U100") (pin "H2") (pinfunction "IO_L41P_GCLK27_M3DQ4_3_H2") (pintype "passive"))
    )
    (net (code "97") (name "/DDR3_DQ5") (class "Default")
      (node (ref "U100") (pin "H1") (pinfunction "IO_L41N_GCLK26_M3DQ5_3_H1") (pintype "passive"))
    )
    (net (code "98") (name "/DDR3_DQ6") (class "Default")
      (node (ref "U100") (pin "J3") (pinfunction "IO_L40P_M3DQ6_3_J3") (pintype "passive"))
    )
    (net (code "99") (name "/DDR3_DQ7") (class "Default")
      (node (ref "U100") (pin "J1") (pinfunction "IO_L40N_M3DQ7_3_J1") (pintype "passive"))
    )
    (net (code "100") (name "/DDR3_DQ8") (class "Default")
      (node (ref "U100") (pin "M3") (pinfunction "IO_L36P_M3DQ8_3_M3") (pintype "passive"))
    )
    (net (code "101") (name "/DDR3_DQ9") (class "Default")
      (node (ref "U100") (pin "M1") (pinfunction "IO_L36N_M3DQ9_3_M1") (pintype "passive"))
    )
    (net (code "102") (name "/DDR3_DQ10") (class "Default")
      (node (ref "U100") (pin "N2") (pinfunction "IO_L35P_M3DQ10_3_N2") (pintype "passive"))
    )
    (net (code "103") (name "/DDR3_DQ11") (class "Default")
      (node (ref "U100") (pin "N1") (pinfunction "IO_L35N_M3DQ11_3_N1") (pintype "passive"))
    )
    (net (code "104") (name "/DDR3_DQ12") (class "Default")
      (node (ref "U100") (pin "T2") (pinfunction "IO_L33P_M3DQ12_3_T2") (pintype "passive"))
    )
    (net (code "105") (name "/DDR3_DQ13") (class "Default")
      (node (ref "U100") (pin "T1") (pinfunction "IO_L33N_M3DQ13_3_T1") (pintype "passive"))
    )
    (net (code "106") (name "/DDR3_DQ14") (class "Default")
      (node (ref "U100") (pin "U2") (pinfunction "IO_L32P_M3DQ14_3_U2") (pintype "passive"))
    )
    (net (code "107") (name "/DDR3_DQ15") (class "Default")
      (node (ref "U100") (pin "U1") (pinfunction "IO_L32N_M3DQ15_3_U1") (pintype "passive"))
    )
    (net (code "108") (name "/DDR3_LDM") (class "Default")
      (node (ref "U100") (pin "K3") (pinfunction "IO_L42N_GCLK24_M3LDM_3_K3") (pintype "passive"))
    )
    (net (code "109") (name "/DDR3_LDQS_N") (class "Default")
      (node (ref "U100") (pin "L3") (pinfunction "IO_L39N_M3LDQSN_3_L3") (pintype "passive"))
    )
    (net (code "110") (name "/DDR3_LDQS_P") (class "Default")
      (node (ref "U100") (pin "L4") (pinfunction "IO_L39P_M3LDQS_3_L4") (pintype "passive"))
    )
    (net (code "111") (name "/DDR3_ODT") (class "Default")
      (node (ref "U100") (pin "K6") (pinfunction "IO_L45N_M3ODT_3_K6") (pintype "passive"))
    )
    (net (code "112") (name "/DDR3_RAS_N") (class "Default")
      (node (ref "U100") (pin "L5") (pinfunction "IO_L43P_GCLK23_M3RASN_3_L5") (pintype "passive"))
    )
    (net (code "113") (name "/DDR3_RESET_N") (class "Default")
      (node (ref "U100") (pin "E4") (pinfunction "IO_L54P_M3RESET_3_E4") (pintype "passive"))
    )
    (net (code "114") (name "/DDR3_UDM") (class "Default")
      (node (ref "U100") (pin "K4") (pinfunction "IO_L42P_GCLK25_TRDY2_M3UDM_3_K4") (pintype "passive"))
    )
    (net (code "115") (name "/DDR3_UDQS_N") (class "Default")
      (node (ref "U100") (pin "P1") (pinfunction "IO_L34N_M3UDQSN_3_P1") (pintype "passive"))
    )
    (net (code "116") (name "/DDR3_UDQS_P") (class "Default")
      (node (ref "U100") (pin "P2") (pinfunction "IO_L34P_M3UDQS_3_P2") (pintype "passive"))
    )
    (net (code "117") (name "/DDR3_WE_N") (class "Default")
      (node (ref "U100") (pin "E3") (pinfunction "IO_L50P_M3WE_3_E3") (pintype "passive"))
    )
    (net (code "118") (name "/EEPROM_SCL") (class "Default")
      (node (ref "U100") (pin "U16") (pinfunction "IO_L2P_CMPCLK_2_U16") (pintype "passive"))
    )
    (net (code "119") (name "/EEPROM_SDA") (class "Default")
      (node (ref "U100") (pin "V16") (pinfunction "IO_L2N_CMPMOSI_2_V16") (pintype "passive"))
    )
    (net (code "120") (name "/ESP_MISO") (class "Default")
      (node (ref "U100") (pin "A2") (pinfunction "IO_L2N_0_A2") (pintype "passive"))
    )
    (net (code "121") (name "/ESP_MOSI") (class "Default")
      (node (ref "U100") (pin "B2") (pinfunction "IO_L2P_0_B2") (pintype "passive"))
    )
    (net (code "122") (name "/ESP_SCK") (class "Default")
      (node (ref "U100") (pin "D6") (pinfunction "IO_L3P_0_D6") (pintype "passive"))
    )
    (net (code "123") (name "/E_COL") (class "Default")
      (node (ref "U100") (pin "H13") (pinfunction "IO_L36P_A9_M1BA0_1_H13") (pintype "passive"))
    )
    (net (code "124") (name "/E_CRS") (class "Default")
      (node (ref "U100") (pin "H14") (pinfunction "IO_L36N_A8_M1BA1_1_H14") (pintype "passive"))
    )
    (net (code "125") (name "/E_GTXC") (class "Default")
      (node (ref "U100") (pin "H15") (pinfunction "IO_L37P_A7_M1A0_1_H15") (pintype "passive"))
    )
    (net (code "126") (name "/E_MDC") (class "Default")
      (node (ref "U100") (pin "L15") (pinfunction "IO_L42P_GCLK7_M1UDM_1_L15") (pintype "passive"))
    )
    (net (code "127") (name "/E_MDIO") (class "Default")
      (node (ref "U100") (pin "L16") (pinfunction "IO_L42N_GCLK6_TRDY1_M1LDM_1_L16") (pintype "passive"))
    )
    (net (code "128") (name "/E_RESET") (class "Default")
      (node (ref "U100") (pin "J16") (pinfunction "IO_L44P_A3_M1DQ6_1_J16") (pintype "passive"))
    )
    (net (code "129") (name "/E_RXC") (class "Default")
      (node (ref "U100") (pin "F18") (pinfunction "IO_L35N_A10_M1A2_1_F18") (pintype "passive"))
    )
    (net (code "130") (name "/E_RXD0") (class "Default")
      (node (ref "U100") (pin "D18") (pinfunction "IO_L31N_A18_M1A12_1_D18") (pintype "passive"))
    )
    (net (code "131") (name "/E_RXD1") (class "Default")
      (node (ref "U100") (pin "E16") (pinfunction "IO_L33P_A15_M1A10_1_E16") (pintype "passive"))
    )
    (net (code "132") (name "/E_RXD2") (class "Default")
      (node (ref "U100") (pin "E18") (pinfunction "IO_L33N_A14_M1A4_1_E18") (pintype "passive"))
    )
    (net (code "133") (name "/E_RXD3") (class "Default")
      (node (ref "U100") (pin "F17") (pinfunction "IO_L35P_A11_M1A7_1_F17") (pintype "passive"))
    )
    (net (code "134") (name "/E_RXD4") (class "Default")
      (node (ref "U100") (pin "G13") (pinfunction "IO_L32N_A16_M1A9_1_G13") (pintype "passive"))
    )
    (net (code "135") (name "/E_RXD5") (class "Default")
      (node (ref "U100") (pin "G14") (pinfunction "IO_L30N_A20_M1A11_1_G14") (pintype "passive"))
    )
    (net (code "136") (name "/E_RXD6") (class "Default")
      (node (ref "U100") (pin "G16") (pinfunction "IO_L38P_A5_M1CLK_1_G16") (pintype "passive"))
    )
    (net (code "137") (name "/E_RXD7") (class "Default")
      (node (ref "U100") (pin "G18") (pinfunction "IO_L38N_A4_M1CLKN_1_G18") (pintype "passive"))
    )
    (net (code "138") (name "/E_RXDV") (class "Default")
      (node (ref "U100") (pin "D17") (pinfunction "IO_L31P_A19_M1CKE_1_D17") (pintype "passive"))
    )
    (net (code "139") (name "/E_RXER") (class "Default")
      (node (ref "U100") (pin "H12") (pinfunction "IO_L32P_A17_M1A8_1_H12") (pintype "passive"))
    )
    (net (code "140") (name "/E_TXC") (class "Default")
      (node (ref "U100") (pin "K14") (pinfunction "IO_L39N_M1ODT_1_K14") (pintype "passive"))
    )
    (net (code "141") (name "/E_TXD0") (class "Default")
      (node (ref "U100") (pin "J13") (pinfunction "IO_L39P_M1A3_1_J13") (pintype "passive"))
    )
    (net (code "142") (name "/E_TXD1") (class "Default")
      (node (ref "U100") (pin "J18") (pinfunction "IO_L44N_A2_M1DQ7_1_J18") (pintype "passive"))
    )
    (net (code "143") (name "/E_TXD2") (class "Default")
      (node (ref "U100") (pin "K12") (pinfunction "IO_L34P_A13_M1WE_1_K12") (pintype "passive"))
    )
    (net (code "144") (name "/E_TXD3") (class "Default")
      (node (ref "U100") (pin "K13") (pinfunction "IO_L34N_A12_M1BA2_1_K13") (pintype "passive"))
    )
    (net (code "145") (name "/E_TXD4") (class "Default")
      (node (ref "U100") (pin "K15") (pinfunction "IO_L41P_GCLK9_IRDY1_M1RASN_1_K15") (pintype "passive"))
    )
    (net (code "146") (name "/E_TXD5") (class "Default")
      (node (ref "U100") (pin "K16") (pinfunction "IO_L41N_GCLK8_M1CASN_1_K16") (pintype "passive"))
    )
    (net (code "147") (name "/E_TXD6") (class "Default")
      (node (ref "U100") (pin "K17") (pinfunction "IO_L45P_A1_M1LDQS_1_K17") (pintype "passive"))
    )
    (net (code "148") (name "/E_TXD7") (class "Default")
      (node (ref "U100") (pin "L12") (pinfunction "IO_L40P_GCLK11_M1A5_1_L12") (pintype "passive"))
    )
    (net (code "149") (name "/E_TXEN") (class "Default")
      (node (ref "U100") (pin "H16") (pinfunction "IO_L37N_A6_M1A1_1_H16") (pintype "passive"))
    )
    (net (code "150") (name "/E_TXER") (class "Default")
      (node (ref "U100") (pin "L13") (pinfunction "IO_L40N_GCLK10_M1A6_1_L13") (pintype "passive"))
    )
    (net (code "151") (name "/FPGA_GCLK1") (class "Default")
      (node (ref "R111") (pin "2") (pinfunction "2_2") (pintype "passive"))
      (node (ref "U100") (pin "U10") (pinfunction "IO_L30P_GCLK1_D13_2_U10") (pintype "passive"))
    )
    (net (code "152") (name "/FPGA_M0") (class "Default")
      (node (ref "R105") (pin "1") (pinfunction "1_1") (pintype "passive"))
      (node (ref "U100") (pin "T15") (pinfunction "IO_L1N_M0_CMPMISO_2_T15") (pintype "passive"))
    )
    (net (code "153") (name "/FPGA_M1") (class "Default")
      (node (ref "R104") (pin "1") (pinfunction "1_1") (pintype "passive"))
      (node (ref "U100") (pin "N12") (pinfunction "IO_L13P_M1_2_N12") (pintype "passive"))
    )
    (net (code "154") (name "/FPGA_TCK") (class "Default")
      (node (ref "R108") (pin "2") (pinfunction "2_2") (pintype "passive"))
      (node (ref "U100") (pin "A17") (pinfunction "TCK_A17") (pintype "passive"))
    )
    (net (code "155") (name "/FPGA_TDI") (class "Default")
      (node (ref "R110") (pin "2") (pinfunction "2_2") (pintype "passive"))
      (node (ref "U100") (pin "D15") (pinfunction "TDI_D15") (pintype "passive"))
    )
    (net (code "156") (name "/FPGA_TDO") (class "Default")
      (node (ref "R109") (pin "2") (pinfunction "2_2") (pintype "passive"))
      (node (ref "U100") (pin "D16") (pinfunction "TDO_D16") (pintype "passive"))
    )
    (net (code "157") (name "/FPGA_TMS") (class "Default")
      (node (ref "R106") (pin "2") (pinfunction "2_2") (pintype "passive"))
      (node (ref "U100") (pin "B18") (pinfunction "TMS_B18") (pintype "passive"))
    )
    (net (code "158") (name "/QSPI_CLK") (class "Default")
      (node (ref "U100") (pin "V15") (pinfunction "IO_L5N_2_V15") (pintype "passive"))
    )
    (net (code "159") (name "/QSPI_CS") (class "Default")
      (node (ref "U100") (pin "U15") (pinfunction "IO_L5P_2_U15") (pintype "passive"))
    )
    (net (code "160") (name "/QSPI_MISO0") (class "Default")
      (node (ref "U100") (pin "T13") (pinfunction "IO_L3N_MOSI_CSI_B_MISO0_2_T13") (pintype "passive"))
    )
    (net (code "161") (name "/QSPI_MISO1") (class "Default")
      (node (ref "U100") (pin "R13") (pinfunction "IO_L3P_D0_DIN_MISO_MISO1_2_R13") (pintype "passive"))
    )
    (net (code "162") (name "/QSPI_MISO2") (class "Default")
      (node (ref "U100") (pin "T14") (pinfunction "IO_L12P_D1_MISO2_2_T14") (pintype "passive"))
    )
    (net (code "163") (name "/QSPI_MISO3") (class "Default")
      (node (ref "U100") (pin "V14") (pinfunction "IO_L12N_D2_MISO3_2_V14") (pintype "passive"))
    )
    (net (code "164") (name "/USB_CLKOUT") (class "Default")
      (node (ref "U100") (pin "D9") (pinfunction "IO_L34P_GCLK19_0_D9") (pintype "passive"))
    )
    (net (code "165") (name "/USB_FD0") (class "Default")
      (node (ref "U100") (pin "G9") (pinfunction "IO_L38P_0_G9") (pintype "passive"))
    )
    (net (code "166") (name "/USB_FD1") (class "Default")
      (node (ref "U100") (pin "C6") (pinfunction "IO_L3N_0_C6") (pintype "passive"))
    )
    (net (code "167") (name "/USB_FD2") (class "Default")
      (node (ref "U100") (pin "F9") (pinfunction "IO_L38N_VREF_0_F9") (pintype "passive"))
    )
    (net (code "168") (name "/USB_FD3") (class "Default")
      (node (ref "U100") (pin "A3") (pinfunction "IO_L4N_0_A3") (pintype "passive"))
    )
    (net (code "169") (name "/USB_FD4") (class "Default")
      (node (ref "U100") (pin "D8") (pinfunction "IO_L11P_0_D8") (pintype "passive"))
    )
    (net (code "170") (name "/USB_FD5") (class "Default")
      (node (ref "U100") (pin "B3") (pinfunction "IO_L4P_0_B3") (pintype "passive"))
    )
    (net (code "171") (name "/USB_FD6") (class "Default")
      (node (ref "U100") (pin "C5") (pinfunction "IO_L6P_0_C5") (pintype "passive"))
    )
    (net (code "172") (name "/USB_FD7") (class "Default")
      (node (ref "U100") (pin "A4") (pinfunction "IO_L5N_0_A4") (pintype "passive"))
    )
    (net (code "173") (name "/USB_FD8") (class "Default")
      (node (ref "U100") (pin "C8") (pinfunction "IO_L11N_0_C8") (pintype "passive"))
    )
    (net (code "174") (name "/USB_FD9") (class "Default")
      (node (ref "U100") (pin "A7") (pinfunction "IO_L10N_0_A7") (pintype "passive"))
    )
    (net (code "175") (name "/USB_FD10") (class "Default")
      (node (ref "U100") (pin "B6") (pinfunction "IO_L8P_0_B6") (pintype "passive"))
    )
    (net (code "176") (name "/USB_FD11") (class "Default")
      (node (ref "U100") (pin "A6") (pinfunction "IO_L8N_VREF_0_A6") (pintype "passive"))
    )
    (net (code "177") (name "/USB_FD12") (class "Default")
      (node (ref "U100") (pin "C10") (pinfunction "IO_L37P_GCLK13_0_C10") (pintype "passive"))
    )
    (net (code "178") (name "/USB_FD13") (class "Default")
      (node (ref "U100") (pin "D11") (pinfunction "IO_L36P_GCLK15_0_D11") (pintype "passive"))
    )
    (net (code "179") (name "/USB_FD14") (class "Default")
      (node (ref "U100") (pin "B12") (pinfunction "IO_L41P_0_B12") (pintype "passive"))
    )
    (net (code "180") (name "/USB_FD15") (class "Default")
      (node (ref "U100") (pin "C11") (pinfunction "IO_L36N_GCLK14_0_C11") (pintype "passive"))
    )
    (net (code "181") (name "/USB_FIFOADR0") (class "Default")
      (node (ref "U100") (pin "A9") (pinfunction "IO_L35N_GCLK16_0_A9") (pintype "passive"))
    )
    (net (code "182") (name "/USB_FIFOADR1") (class "Default")
      (node (ref "U100") (pin "B8") (pinfunction "IO_L33P_0_B8") (pintype "passive"))
    )
    (net (code "183") (name "/USB_FLAGA") (class "Default")
      (node (ref "U100") (pin "B4") (pinfunction "IO_L5P_0_B4") (pintype "passive"))
    )
    (net (code "184") (name "/USB_FLAGB") (class "Default")
      (node (ref "U100") (pin "A5") (pinfunction "IO_L6N_0_A5") (pintype "passive"))
    )
    (net (code "185") (name "/USB_FLAGC") (class "Default")
      (node (ref "U100") (pin "C7") (pinfunction "IO_L10P_0_C7") (pintype "passive"))
    )
    (net (code "186") (name "/USB_IFCLK") (class "Default")
      (node (ref "U100") (pin "C9") (pinfunction "IO_L34N_GCLK18_0_C9") (pintype "passive"))
    )
    (net (code "187") (name "/USB_PKTEND") (class "Default")
      (node (ref "U100") (pin "B9") (pinfunction "IO_L35P_GCLK17_0_B9") (pintype "passive"))
    )
    (net (code "188") (name "/USB_SLCS") (class "Default")
      (node (ref "U100") (pin "A11") (pinfunction "IO_L39N_0_A11") (pintype "passive"))
    )
    (net (code "189") (name "/USB_SLOE") (class "Default")
      (node (ref "U100") (pin "A8") (pinfunction "IO_L33N_0_A8") (pintype "passive"))
    )
    (net (code "190") (name "/USB_SLRD") (class "Default")
      (node (ref "U100") (pin "B11") (pinfunction "IO_L39P_0_B11") (pintype "passive"))
    )
    (net (code "191") (name "/USB_SLWR") (class "Default")
      (node (ref "U100") (pin "A10") (pinfunction "IO_L37N_GCLK12_0_A10") (pintype "passive"))
    )
    (net (code "192") (name "/VGA_B0") (class "Default")
      (node (ref "U100") (pin "U17") (pinfunction "IO_L52P_M1DQ14_1_U17") (pintype "passive"))
    )
    (net (code "193") (name "/VGA_B1") (class "Default")
      (node (ref "U100") (pin "T18") (pinfunction "IO_L51N_M1DQ13_1_T18") (pintype "passive"))
    )
    (net (code "194") (name "/VGA_B2") (class "Default")
      (node (ref "U100") (pin "P17") (pinfunction "IO_L49P_M1DQ10_1_P17") (pintype "passive"))
    )
    (net (code "195") (name "/VGA_B3") (class "Default")
      (node (ref "U100") (pin "P18") (pinfunction "IO_L49N_M1DQ11_1_P18") (pintype "passive"))
    )
    (net (code "196") (name "/VGA_B4") (class "Default")
      (node (ref "U100") (pin "P16") (pinfunction "IO_L74N_DOUT_BUSY_1_P16") (pintype "passive"))
    )
    (net (code "197") (name "/VGA_G0") (class "Default")
      (node (ref "U100") (pin "U18") (pinfunction "IO_L52N_M1DQ15_1_U18") (pintype "passive"))
    )
    (net (code "198") (name "/VGA_G1") (class "Default")
      (node (ref "U100") (pin "T17") (pinfunction "IO_L51P_M1DQ12_1_T17") (pintype "passive"))
    )
    (net (code "199") (name "/VGA_G2") (class "Default")
      (node (ref "U100") (pin "L18") (pinfunction "IO_L46N_FOE_B_M1DQ3_1_L18") (pintype "passive"))
    )
    (net (code "200") (name "/VGA_G3") (class "Default")
      (node (ref "U100") (pin "N16") (pinfunction "IO_L50N_M1UDQSN_1_N16") (pintype "passive"))
    )
    (net (code "201") (name "/VGA_G4") (class "Default")
      (node (ref "U100") (pin "P15") (pinfunction "IO_L74P_AWAKE_1_P15") (pintype "passive"))
    )
    (net (code "202") (name "/VGA_G5") (class "Default")
      (node (ref "U100") (pin "N15") (pinfunction "IO_L50P_M1UDQS_1_N15") (pintype "passive"))
    )
    (net (code "203") (name "/VGA_HS") (class "Default")
      (node (ref "U100") (pin "L14") (pinfunction "IO_L61P_1_L14") (pintype "passive"))
    )
    (net (code "204") (name "/VGA_R0") (class "Default")
      (node (ref "U100") (pin "N18") (pinfunction "IO_L48N_M1DQ9_1_N18") (pintype "passive"))
    )
    (net (code "205") (name "/VGA_R1") (class "Default")
      (node (ref "U100") (pin "M18") (pinfunction "IO_L47N_LDC_M1DQ1_1_M18") (pintype "passive"))
    )
    (net (code "206") (name "/VGA_R2") (class "Default")
      (node (ref "U100") (pin "N17") (pinfunction "IO_L48P_HDC_M1DQ8_1_N17") (pintype "passive"))
    )
    (net (code "207") (name "/VGA_R3") (class "Default")
      (node (ref "U100") (pin "M14") (pinfunction "IO_L53P_1_M14") (pintype "passive"))
    )
    (net (code "208") (name "/VGA_R4") (class "Default")
      (node (ref "U100") (pin "N14") (pinfunction "IO_L53N_VREF_1_N14") (pintype "passive"))
    )
    (net (code "209") (name "/VGA_VS") (class "Default")
      (node (ref "U100") (pin "M13") (pinfunction "IO_L61N_1_M13") (pintype "passive"))
    )
    (net (code "221") (name "DDR3_VREF") (class "Default")
      (node (ref "C100") (pin "2") (pinfunction "2_2") (pintype "passive"))
      (node (ref "U100") (pin "C1") (pinfunction "IO_L83N_VREF_3_C1") (pintype "passive"))
      (node (ref "U100") (pin "M5") (pinfunction "IO_L31N_VREF_3_M5") (pintype "passive"))
      (node (ref "U100") (pin "N3") (pinfunction "IO_L1N_VREF_3_N3") (pintype "passive"))
    )
    (net (code "222") (name "DGND") (class "Default")
      (node (ref "C100") (pin "1") (pinfunction "1_1") (pintype "passive"))
      (node (ref "C101") (pin "1") (pinfunction "1_1") (pintype "passive"))
      (node (ref "C102") (pin "1") (pinfunction "1_1") (pintype "passive"))
      (node (ref "C103") (pin "1") (pinfunction "1_1") (pintype "passive"))
      (node (ref "C104") (pin "1") (pinfunction "1_1") (pintype "passive"))
      (node (ref "C105") (pin "1") (pinfunction "1_1") (pintype "passive"))
      (node (ref "C106") (pin "1") (pinfunction "1_1") (pintype "passive"))
      (node (ref "C107") (pin "1") (pinfunction "1_1") (pintype "passive"))
      (node (ref "C108") (pin "1") (pinfunction "1_1") (pintype "passive"))
      (node (ref "C109") (pin "1") (pinfunction "1_1") (pintype "passive"))
      (node (ref "C110") (pin "1") (pinfunction "1_1") (pintype "passive"))
      (node (ref "C111") (pin "1") (pinfunction "1_1") (pintype "passive"))
      (node (ref "C112") (pin "1") (pinfunction "1_1") (pintype "passive"))
      (node (ref "C113") (pin "1") (pinfunction "1_1") (pintype "passive"))
      (node (ref "C114") (pin "1") (pinfunction "1_1") (pintype "passive"))
      (node (ref "C115") (pin "1") (pinfunction "1_1") (pintype "passive"))
      (node (ref "C116") (pin "1") (pinfunction "1_1") (pintype "passive"))
      (node (ref "C117") (pin "1") (pinfunction "1_1") (pintype "passive"))
      (node (ref "C118") (pin "1") (pinfunction "1_1") (pintype "passive"))
      (node (ref "C119") (pin "1") (pinfunction "1_1") (pintype "passive"))
      (node (ref "C120") (pin "1") (pinfunction "1_1") (pintype "passive"))
      (node (ref "C121") (pin "1") (pinfunction "1_1") (pintype "passive"))
      (node (ref "C122") (pin "1") (pinfunction "1_1") (pintype "passive"))
      (node (ref "C123") (pin "1") (pinfunction "1_1") (pintype "passive"))
      (node (ref "C124") (pin "1") (pinfunction "1_1") (pintype "passive"))
      (node (ref "C125") (pin "1") (pinfunction "1_1") (pintype "passive"))
      (node (ref "C126") (pin "1") (pinfunction "1_1") (pintype "passive"))
      (node (ref "C127") (pin "1") (pinfunction "1_1") (pintype "passive"))
      (node (ref "C128") (pin "1") (pinfunction "1_1") (pintype "passive"))
      (node (ref "C129") (pin "1") (pinfunction "1_1") (pintype "passive"))
      (node (ref "C130") (pin "1") (pinfunction "1_1") (pintype "passive"))
      (node (ref "C131") (pin "1") (pinfunction "1_1") (pintype "passive"))
      (node (ref "C132") (pin "1") (pinfunction "1_1") (pintype "passive"))
      (node (ref "C133") (pin "1") (pinfunction "1_1") (pintype "passive"))
      (node (ref "C134") (pin "1") (pinfunction "1_1") (pintype "passive"))
      (node (ref "C135") (pin "1") (pinfunction "1_1") (pintype "passive"))
      (node (ref "C136") (pin "1") (pinfunction "1_1") (pintype "passive"))
      (node (ref "C137") (pin "1") (pinfunction "1_1") (pintype "passive"))
      (node (ref "C138") (pin "1") (pinfunction "1_1") (pintype "passive"))
      (node (ref "JTAG") (pin "1") (pinfunction "1_1") (pintype "passive"))
      (node (ref "JTAG") (pin "11") (pinfunction "11_11") (pintype "passive"))
      (node (ref "JTAG") (pin "3") (pinfunction "3_3") (pintype "passive"))
      (node (ref "JTAG") (pin "5") (pinfunction "5_5") (pintype "passive"))
      (node (ref "JTAG") (pin "7") (pinfunction "7_7") (pintype "passive"))
      (node (ref "JTAG") (pin "9") (pinfunction "9_9") (pintype "passive"))
      (node (ref "R100") (pin "1") (pinfunction "1_1") (pintype "passive"))
      (node (ref "R103") (pin "1") (pinfunction "1_1") (pintype "passive"))
      (node (ref "R105") (pin "2") (pinfunction "2_2") (pintype "passive"))
      (node (ref "R107") (pin "1") (pinfunction "1_1") (pintype "passive"))
      (node (ref "U100") (pin "A1") (pinfunction "GND_A1") (pintype "power_in"))
      (node (ref "U100") (pin "A18") (pinfunction "GND_A18") (pintype "power_in"))
      (node (ref "U100") (pin "B13") (pinfunction "GND_B13") (pintype "power_in"))
      (node (ref "U100") (pin "B7") (pinfunction "GND_B7") (pintype "power_in"))
      (node (ref "U100") (pin "C16") (pinfunction "GND_C16") (pintype "power_in"))
      (node (ref "U100") (pin "C3") (pinfunction "GND_C3") (pintype "power_in"))
      (node (ref "U100") (pin "D10") (pinfunction "GND_D10") (pintype "power_in"))
      (node (ref "U100") (pin "D5") (pinfunction "GND_D5") (pintype "power_in"))
      (node (ref "U100") (pin "E15") (pinfunction "GND_E15") (pintype "power_in"))
      (node (ref "U100") (pin "G12") (pinfunction "GND_G12") (pintype "power_in"))
      (node (ref "U100") (pin "G17") (pinfunction "GND_G17") (pintype "power_in"))
      (node (ref "U100") (pin "G2") (pinfunction "GND_G2") (pintype "power_in"))
      (node (ref "U100") (pin "G5") (pinfunction "GND_G5") (pintype "power_in"))
      (node (ref "U100") (pin "H10") (pinfunction "GND_H10") (pintype "power_in"))
      (node (ref "U100") (pin "H8") (pinfunction "GND_H8") (pintype "power_in"))
      (node (ref "U100") (pin "J11") (pinfunction "GND_J11") (pintype "power_in"))
      (node (ref "U100") (pin "J15") (pinfunction "GND_J15") (pintype "power_in"))
      (node (ref "U100") (pin "J4") (pinfunction "GND_J4") (pintype "power_in"))
      (node (ref "U100") (pin "J9") (pinfunction "GND_J9") (pintype "power_in"))
      (node (ref "U100") (pin "K10") (pinfunction "GND_K10") (pintype "power_in"))
      (node (ref "U100") (pin "K8") (pinfunction "GND_K8") (pintype "power_in"))
      (node (ref "U100") (pin "L11") (pinfunction "GND_L11") (pintype "power_in"))
      (node (ref "U100") (pin "L9") (pinfunction "GND_L9") (pintype "power_in"))
      (node (ref "U100") (pin "M17") (pinfunction "GND_M17") (pintype "power_in"))
      (node (ref "U100") (pin "M2") (pinfunction "GND_M2") (pintype "power_in"))
      (node (ref "U100") (pin "M6") (pinfunction "GND_M6") (pintype "power_in"))
      (node (ref "U100") (pin "N13") (pinfunction "GND_N13") (pintype "power_in"))
      (node (ref "U100") (pin "R1") (pinfunction "GND_R1") (pintype "power_in"))
      (node (ref "U100") (pin "R14") (pinfunction "GND_R14") (pintype "power_in"))
      (node (ref "U100") (pin "R18") (pinfunction "GND_R18") (pintype "power_in"))
      (node (ref "U100") (pin "R4") (pinfunction "GND_R4") (pintype "power_in"))
      (node (ref "U100") (pin "R9") (pinfunction "GND_R9") (pintype "power_in"))
      (node (ref "U100") (pin "T16") (pinfunction "GND_T16") (pintype "power_in"))
      (node (ref "U100") (pin "U12") (pinfunction "GND_U12") (pintype "power_in"))
      (node (ref "U100") (pin "U6") (pinfunction "GND_U6") (pintype "power_in"))
      (node (ref "U100") (pin "V1") (pinfunction "GND_V1") (pintype "power_in"))
      (node (ref "U100") (pin "V18") (pinfunction "GND_V18") (pintype "power_in"))
      (node (ref "U101") (pin "2") (pinfunction "GND_2") (pintype "passive"))
    )
    (net (code "223") (name "Net-(JTAG-Pad4)") (class "Default")
      (node (ref "JTAG") (pin "4") (pinfunction "4_4") (pintype "passive"))
      (node (ref "R106") (pin "1") (pinfunction "1_1") (pintype "passive"))
    )
    (net (code "224") (name "Net-(JTAG-Pad6)") (class "Default")
      (node (ref "JTAG") (pin "6") (pinfunction "6_6") (pintype "passive"))
      (node (ref "R108") (pin "1") (pinfunction "1_1") (pintype "passive"))
    )
    (net (code "225") (name "Net-(JTAG-Pad8)") (class "Default")
      (node (ref "JTAG") (pin "8") (pinfunction "8_8") (pintype "passive"))
      (node (ref "R109") (pin "1") (pinfunction "1_1") (pintype "passive"))
    )
    (net (code "226") (name "Net-(JTAG-Pad10)") (class "Default")
      (node (ref "JTAG") (pin "10") (pinfunction "10_10") (pintype "passive"))
      (node (ref "R110") (pin "1") (pinfunction "1_1") (pintype "passive"))
    )
    (net (code "227") (name "Net-(U100A-IO_L1P_HSWAPEN_0)") (class "Default")
      (node (ref "R103") (pin "2") (pinfunction "2_2") (pintype "passive"))
      (node (ref "U100") (pin "D4") (pinfunction "IO_L1P_HSWAPEN_0_D4") (pintype "passive"))
    )
    (net (code "228") (name "Net-(U100C-CMPCS_B_2)") (class "Default")
      (node (ref "R102") (pin "2") (pinfunction "2_2") (pintype "passive"))
      (node (ref "U100") (pin "P13") (pinfunction "CMPCS_B_2_P13") (pintype "passive"))
    )
    (net (code "229") (name "Net-(U100D-IO_L2N_3)") (class "Default")
      (node (ref "R101") (pin "2") (pinfunction "2_2") (pintype "passive"))
      (node (ref "U100") (pin "P3") (pinfunction "IO_L2N_3_P3") (pintype "passive"))
    )
    (net (code "230") (name "Net-(U100D-IO_L83P_3)") (class "Default")
      (node (ref "R100") (pin "2") (pinfunction "2_2") (pintype "passive"))
      (node (ref "U100") (pin "C2") (pinfunction "IO_L83P_3_C2") (pintype "passive"))
    )
    (net (code "231") (name "Net-(U100H-SUSPEND)") (class "Default")
      (node (ref "R107") (pin "2") (pinfunction "2_2") (pintype "passive"))
      (node (ref "U100") (pin "R16") (pinfunction "SUSPEND_R16") (pintype "passive"))
    )
    (net (code "232") (name "Net-(U101-OE)") (class "Default")
      (node (ref "R112") (pin "2") (pinfunction "2_2") (pintype "passive"))
      (node (ref "U101") (pin "1") (pinfunction "OE_1") (pintype "passive"))
    )
    (net (code "233") (name "Net-(U101-OUT)") (class "Default")
      (node (ref "R111") (pin "1") (pinfunction "1_1") (pintype "passive"))
      (node (ref "U101") (pin "3") (pinfunction "OUT_3") (pintype "passive"))
    )
    (net (code "234") (name "Net-(U101-VDD)") (class "Default")
      (node (ref "C137") (pin "2") (pinfunction "2_2") (pintype "passive"))
      (node (ref "C138") (pin "2") (pinfunction "2_2") (pintype "passive"))
      (node (ref "L100") (pin "2") (pinfunction "2_2") (pintype "passive"))
      (node (ref "R112") (pin "1") (pinfunction "1_1") (pintype "passive"))
      (node (ref "U101") (pin "4") (pinfunction "VDD_4") (pintype "passive"))
    )
    (net (code "235") (name "VCC1V2") (class "Default")
      (node (ref "C125") (pin "2") (pinfunction "2_2") (pintype "passive"))
      (node (ref "C126") (pin "2") (pinfunction "2_2") (pintype "passive"))
      (node (ref "C127") (pin "2") (pinfunction "2_2") (pintype "passive"))
      (node (ref "C128") (pin "2") (pinfunction "2_2") (pintype "passive"))
      (node (ref "C129") (pin "2") (pinfunction "2_2") (pintype "passive"))
      (node (ref "C130") (pin "2") (pinfunction "2_2") (pintype "passive"))
      (node (ref "U100") (pin "G7") (pinfunction "VCCINT_G7") (pintype "power_in"))
      (node (ref "U100") (pin "H11") (pinfunction "VCCINT_H11") (pintype "power_in"))
      (node (ref "U100") (pin "H9") (pinfunction "VCCINT_H9") (pintype "power_in"))
      (node (ref "U100") (pin "J10") (pinfunction "VCCINT_J10") (pintype "power_in"))
      (node (ref "U100") (pin "J8") (pinfunction "VCCINT_J8") (pintype "power_in"))
      (node (ref "U100") (pin "K11") (pinfunction "VCCINT_K11") (pintype "power_in"))
      (node (ref "U100") (pin "K9") (pinfunction "VCCINT_K9") (pintype "power_in"))
      (node (ref "U100") (pin "L10") (pinfunction "VCCINT_L10") (pintype "power_in"))
      (node (ref "U100") (pin "L8") (pinfunction "VCCINT_L8") (pintype "power_in"))
      (node (ref "U100") (pin "M12") (pinfunction "VCCINT_M12") (pintype "power_in"))
      (node (ref "U100") (pin "M7") (pinfunction "VCCINT_M7") (pintype "power_in"))
    )
    (net (code "236") (name "VCC1V5") (class "Default")
      (node (ref "C113") (pin "2") (pinfunction "2_2") (pintype "passive"))
      (node (ref "C114") (pin "2") (pinfunction "2_2") (pintype "passive"))
      (node (ref "C115") (pin "2") (pinfunction "2_2") (pintype "passive"))
      (node (ref "C116") (pin "2") (pinfunction "2_2") (pintype "passive"))
      (node (ref "C117") (pin "2") (pinfunction "2_2") (pintype "passive"))
      (node (ref "C118") (pin "2") (pinfunction "2_2") (pintype "passive"))
      (node (ref "R101") (pin "1") (pinfunction "1_1") (pintype "passive"))
      (node (ref "U100") (pin "E2") (pinfunction "VCCO_3_E2") (pintype "power_in"))
      (node (ref "U100") (pin "G4") (pinfunction "VCCO_3_G4") (pintype "power_in"))
      (node (ref "U100") (pin "J2") (pinfunction "VCCO_3_J2") (pintype "power_in"))
      (node (ref "U100") (pin "J5") (pinfunction "VCCO_3_J5") (pintype "power_in"))
      (node (ref "U100") (pin "M4") (pinfunction "VCCO_3_M4") (pintype "power_in"))
      (node (ref "U100") (pin "R2") (pinfunction "VCCO_3_R2") (pintype "power_in"))
    )
    (net (code "237") (name "VCC3V3") (class "Default")
      (node (ref "C101") (pin "2") (pinfunction "2_2") (pintype "passive"))
      (node (ref "C102") (pin "2") (pinfunction "2_2") (pintype "passive"))
      (node (ref "C103") (pin "2") (pinfunction "2_2") (pintype "passive"))
      (node (ref "C104") (pin "2") (pinfunction "2_2") (pintype "passive"))
      (node (ref "C105") (pin "2") (pinfunction "2_2") (pintype "passive"))
      (node (ref "C106") (pin "2") (pinfunction "2_2") (pintype "passive"))
      (node (ref "C107") (pin "2") (pinfunction "2_2") (pintype "passive"))
      (node (ref "C108") (pin "2") (pinfunction "2_2") (pintype "passive"))
      (node (ref "C109") (pin "2") (pinfunction "2_2") (pintype "passive"))
      (node (ref "C110") (pin "2") (pinfunction "2_2") (pintype "passive"))
      (node (ref "C111") (pin "2") (pinfunction "2_2") (pintype "passive"))
      (node (ref "C112") (pin "2") (pinfunction "2_2") (pintype "passive"))
      (node (ref "C119") (pin "2") (pinfunction "2_2") (pintype "passive"))
      (node (ref "C120") (pin "2") (pinfunction "2_2") (pintype "passive"))
      (node (ref "C121") (pin "2") (pinfunction "2_2") (pintype "passive"))
      (node (ref "C122") (pin "2") (pinfunction "2_2") (pintype "passive"))
      (node (ref "C123") (pin "2") (pinfunction "2_2") (pintype "passive"))
      (node (ref "C124") (pin "2") (pinfunction "2_2") (pintype "passive"))
      (node (ref "C131") (pin "2") (pinfunction "2_2") (pintype "passive"))
      (node (ref "C132") (pin "2") (pinfunction "2_2") (pintype "passive"))
      (node (ref "C133") (pin "2") (pinfunction "2_2") (pintype "passive"))
      (node (ref "C134") (pin "2") (pinfunction "2_2") (pintype "passive"))
      (node (ref "C135") (pin "2") (pinfunction "2_2") (pintype "passive"))
      (node (ref "C136") (pin "2") (pinfunction "2_2") (pintype "passive"))
      (node (ref "JTAG") (pin "2") (pinfunction "2_2") (pintype "passive"))
      (node (ref "L100") (pin "1") (pinfunction "1_1") (pintype "passive"))
      (node (ref "R102") (pin "1") (pinfunction "1_1") (pintype "passive"))
      (node (ref "R104") (pin "2") (pinfunction "2_2") (pintype "passive"))
      (node (ref "U100") (pin "B1") (pinfunction "VCCAUX_B1") (pintype "power_in"))
      (node (ref "U100") (pin "B10") (pinfunction "VCCO_0_B10") (pintype "power_in"))
      (node (ref "U100") (pin "B15") (pinfunction "VCCO_0_B15") (pintype "power_in"))
      (node (ref "U100") (pin "B17") (pinfunction "VCCAUX_B17") (pintype "power_in"))
      (node (ref "U100") (pin "B5") (pinfunction "VCCO_0_B5") (pintype "power_in"))
      (node (ref "U100") (pin "D13") (pinfunction "VCCO_0_D13") (pintype "power_in"))
      (node (ref "U100") (pin "D7") (pinfunction "VCCO_0_D7") (pintype "power_in"))
      (node (ref "U100") (pin "E10") (pinfunction "VCCO_0_E10") (pintype "power_in"))
      (node (ref "U100") (pin "E14") (pinfunction "VCCAUX_E14") (pintype "power_in"))
      (node (ref "U100") (pin "E17") (pinfunction "VCCO_1_E17") (pintype "power_in"))
      (node (ref "U100") (pin "E5") (pinfunction "VCCAUX_E5") (pintype "power_in"))
      (node (ref "U100") (pin "E9") (pinfunction "VCCAUX_E9") (pintype "power_in"))
      (node (ref "U100") (pin "G10") (pinfunction "VCCAUX_G10") (pintype "power_in"))
      (node (ref "U100") (pin "G15") (pinfunction "VCCO_1_G15") (pintype "power_in"))
      (node (ref "U100") (pin "J12") (pinfunction "VCCAUX_J12") (pintype "power_in"))
      (node (ref "U100") (pin "J14") (pinfunction "VCCO_1_J14") (pintype "power_in"))
      (node (ref "U100") (pin "J17") (pinfunction "VCCO_1_J17") (pintype "power_in"))
      (node (ref "U100") (pin "K7") (pinfunction "VCCAUX_K7") (pintype "power_in"))
      (node (ref "U100") (pin "M15") (pinfunction "VCOO_1_M15") (pintype "power_in"))
      (node (ref "U100") (pin "M9") (pinfunction "VCCAUX_M9") (pintype "power_in"))
      (node (ref "U100") (pin "P10") (pinfunction "VCCAUX_P10") (pintype "power_in"))
      (node (ref "U100") (pin "P14") (pinfunction "VCCAUX_P14") (pintype "power_in"))
      (node (ref "U100") (pin "P5") (pinfunction "VCCAUX_P5") (pintype "power_in"))
      (node (ref "U100") (pin "P9") (pinfunction "VCCO_2_P9") (pintype "power_in"))
      (node (ref "U100") (pin "R12") (pinfunction "VCCO_2_R12") (pintype "power_in"))
      (node (ref "U100") (pin "R17") (pinfunction "VCCO_1_R17") (pintype "power_in"))
      (node (ref "U100") (pin "R6") (pinfunction "VCCO_2_R6") (pintype "power_in"))
      (node (ref "U100") (pin "U14") (pinfunction "VCCO_2_U14") (pintype "power_in"))
      (node (ref "U100") (pin "U4") (pinfunction "VCCO_2_U4") (pintype "power_in"))
      (node (ref "U100") (pin "U9") (pinfunction "VCCO_2_U9") (pintype "power_in"))
    )
    (net (code "238") (name "unconnected-(JTAG-Pad12)") (class "Default")
      (node (ref "JTAG") (pin "12") (pinfunction "12_12") (pintype "passive+no_connect"))
    )
    (net (code "239") (name "unconnected-(U100A-IO_L1N_VREF_0-PadC4)") (class "Default")
      (node (ref "U100") (pin "C4") (pinfunction "IO_L1N_VREF_0_C4") (pintype "passive+no_connect"))
    )
    (net (code "240") (name "unconnected-(U100A-IO_L7N_0-PadE6)") (class "Default")
      (node (ref "U100") (pin "E6") (pinfunction "IO_L7N_0_E6") (pintype "passive+no_connect"))
    )
    (net (code "241") (name "unconnected-(U100A-IO_L7P_0-PadF7)") (class "Default")
      (node (ref "U100") (pin "F7") (pinfunction "IO_L7P_0_F7") (pintype "passive+no_connect"))
    )
    (net (code "242") (name "unconnected-(U100A-IO_L9N_0-PadE8)") (class "Default")
      (node (ref "U100") (pin "E8") (pinfunction "IO_L9N_0_E8") (pintype "passive+no_connect"))
    )
    (net (code "243") (name "unconnected-(U100A-IO_L9P_0-PadE7)") (class "Default")
      (node (ref "U100") (pin "E7") (pinfunction "IO_L9P_0_E7") (pintype "passive+no_connect"))
    )
    (net (code "244") (name "unconnected-(U100A-IO_L32N_0-PadF8)") (class "Default")
      (node (ref "U100") (pin "F8") (pinfunction "IO_L32N_0_F8") (pintype "passive+no_connect"))
    )
    (net (code "245") (name "unconnected-(U100A-IO_L32P_0-PadG8)") (class "Default")
      (node (ref "U100") (pin "G8") (pinfunction "IO_L32P_0_G8") (pintype "passive+no_connect"))
    )
    (net (code "246") (name "unconnected-(U100A-IO_L40N_0-PadF10)") (class "Default")
      (node (ref "U100") (pin "F10") (pinfunction "IO_L40N_0_F10") (pintype "passive+no_connect"))
    )
    (net (code "247") (name "unconnected-(U100A-IO_L40P_0-PadG11)") (class "Default")
      (node (ref "U100") (pin "G11") (pinfunction "IO_L40P_0_G11") (pintype "passive+no_connect"))
    )
    (net (code "248") (name "unconnected-(U100A-IO_L41N_0-PadA12)") (class "Default")
      (node (ref "U100") (pin "A12") (pinfunction "IO_L41N_0_A12") (pintype "passive+no_connect"))
    )
    (net (code "249") (name "unconnected-(U100A-IO_L42N_0-PadE11)") (class "Default")
      (node (ref "U100") (pin "E11") (pinfunction "IO_L42N_0_E11") (pintype "passive+no_connect"))
    )
    (net (code "250") (name "unconnected-(U100A-IO_L42P_0-PadF11)") (class "Default")
      (node (ref "U100") (pin "F11") (pinfunction "IO_L42P_0_F11") (pintype "passive+no_connect"))
    )
    (net (code "251") (name "unconnected-(U100A-IO_L47N_0-PadC12)") (class "Default")
      (node (ref "U100") (pin "C12") (pinfunction "IO_L47N_0_C12") (pintype "passive+no_connect"))
    )
    (net (code "252") (name "unconnected-(U100A-IO_L47P_0-PadD12)") (class "Default")
      (node (ref "U100") (pin "D12") (pinfunction "IO_L47P_0_D12") (pintype "passive+no_connect"))
    )
    (net (code "253") (name "unconnected-(U100A-IO_L63N_SCP6_0-PadE13)") (class "Default")
      (node (ref "U100") (pin "E13") (pinfunction "IO_L63N_SCP6_0_E13") (pintype "passive+no_connect"))
    )
    (net (code "254") (name "unconnected-(U100B-IO_L1N_A24_VREF_1-PadF16)") (class "Default")
      (node (ref "U100") (pin "F16") (pinfunction "IO_L1N_A24_VREF_1_F16") (pintype "passive+no_connect"))
    )
    (net (code "255") (name "unconnected-(U100B-IO_L1P_A25_1-PadF15)") (class "Default")
      (node (ref "U100") (pin "F15") (pinfunction "IO_L1P_A25_1_F15") (pintype "passive+no_connect"))
    )
    (net (code "256") (name "unconnected-(U100B-IO_L29N_A22_M1A14_1-PadC18)") (class "Default")
      (node (ref "U100") (pin "C18") (pinfunction "IO_L29N_A22_M1A14_1_C18") (pintype "passive+no_connect"))
    )
    (net (code "257") (name "unconnected-(U100B-IO_L29P_A23_M1A13_1-PadC17)") (class "Default")
      (node (ref "U100") (pin "C17") (pinfunction "IO_L29P_A23_M1A13_1_C17") (pintype "passive+no_connect"))
    )
    (net (code "258") (name "unconnected-(U100B-IO_L30P_A21_M1RESET_1-PadF14)") (class "Default")
      (node (ref "U100") (pin "F14") (pinfunction "IO_L30P_A21_M1RESET_1_F14") (pintype "passive+no_connect"))
    )
    (net (code "259") (name "unconnected-(U100B-IO_L43N_GCLK4_M1DQ5_1-PadH18)") (class "Default")
      (node (ref "U100") (pin "H18") (pinfunction "IO_L43N_GCLK4_M1DQ5_1_H18") (pintype "passive+no_connect"))
    )
    (net (code "260") (name "unconnected-(U100B-IO_L43P_GCLK5_M1DQ4_1-PadH17)") (class "Default")
      (node (ref "U100") (pin "H17") (pinfunction "IO_L43P_GCLK5_M1DQ4_1_H17") (pintype "passive+no_connect"))
    )
    (net (code "261") (name "unconnected-(U100B-IO_L45N_A0_M1LDQSN_1-PadK18)") (class "Default")
      (node (ref "U100") (pin "K18") (pinfunction "IO_L45N_A0_M1LDQSN_1_K18") (pintype "passive+no_connect"))
    )
    (net (code "262") (name "unconnected-(U100B-IO_L46P_FCS_B_M1DQ2_1-PadL17)") (class "Default")
      (node (ref "U100") (pin "L17") (pinfunction "IO_L46P_FCS_B_M1DQ2_1_L17") (pintype "passive+no_connect"))
    )
    (net (code "263") (name "unconnected-(U100B-IO_L47P_FWE_B_M1DQ0_1-PadM16)") (class "Default")
      (node (ref "U100") (pin "M16") (pinfunction "IO_L47P_FWE_B_M1DQ0_1_M16") (pintype "passive+no_connect"))
    )
    (net (code "264") (name "unconnected-(U100C-DONE_2-PadV17)") (class "Default")
      (node (ref "U100") (pin "V17") (pinfunction "DONE_2_V17") (pintype "passive+no_connect"))
    )
    (net (code "265") (name "unconnected-(U100C-IO_L13N_D10_2-PadP12)") (class "Default")
      (node (ref "U100") (pin "P12") (pinfunction "IO_L13N_D10_2_P12") (pintype "passive+no_connect"))
    )
    (net (code "266") (name "unconnected-(U100C-IO_L31N_GCLK30_D15_2-PadT8)") (class "Default")
      (node (ref "U100") (pin "T8") (pinfunction "IO_L31N_GCLK30_D15_2_T8") (pintype "passive+no_connect"))
    )
    (net (code "267") (name "unconnected-(U100C-IO_L32P_GCLK29_2-PadT9)") (class "Default")
      (node (ref "U100") (pin "T9") (pinfunction "IO_L32P_GCLK29_2_T9") (pintype "passive+no_connect"))
    )
    (net (code "268") (name "unconnected-(U100C-IO_L40P_2-PadM8)") (class "Default")
      (node (ref "U100") (pin "M8") (pinfunction "IO_L40P_2_M8") (pintype "passive+no_connect"))
    )
    (net (code "269") (name "unconnected-(U100C-PROGRAM_B_2-PadV2)") (class "Default")
      (node (ref "U100") (pin "V2") (pinfunction "PROGRAM_B_2_V2") (pintype "passive+no_connect"))
    )
    (net (code "270") (name "unconnected-(U100D-IO_L1P_3-PadN4)") (class "Default")
      (node (ref "U100") (pin "N4") (pinfunction "IO_L1P_3_N4") (pintype "passive+no_connect"))
    )
    (net (code "271") (name "unconnected-(U100D-IO_L2P_3-PadP4)") (class "Default")
      (node (ref "U100") (pin "P4") (pinfunction "IO_L2P_3_P4") (pintype "passive+no_connect"))
    )
    (net (code "272") (name "unconnected-(U100D-IO_L31P_3-PadL6)") (class "Default")
      (node (ref "U100") (pin "L6") (pinfunction "IO_L31P_3_L6") (pintype "passive+no_connect"))
    )
  )
)
